# SO_DO_DK_TONG_THE_MAY_GHI_HINH_9_9_2021.net
KiCad netlist of a schematic drawn in Altium Designer
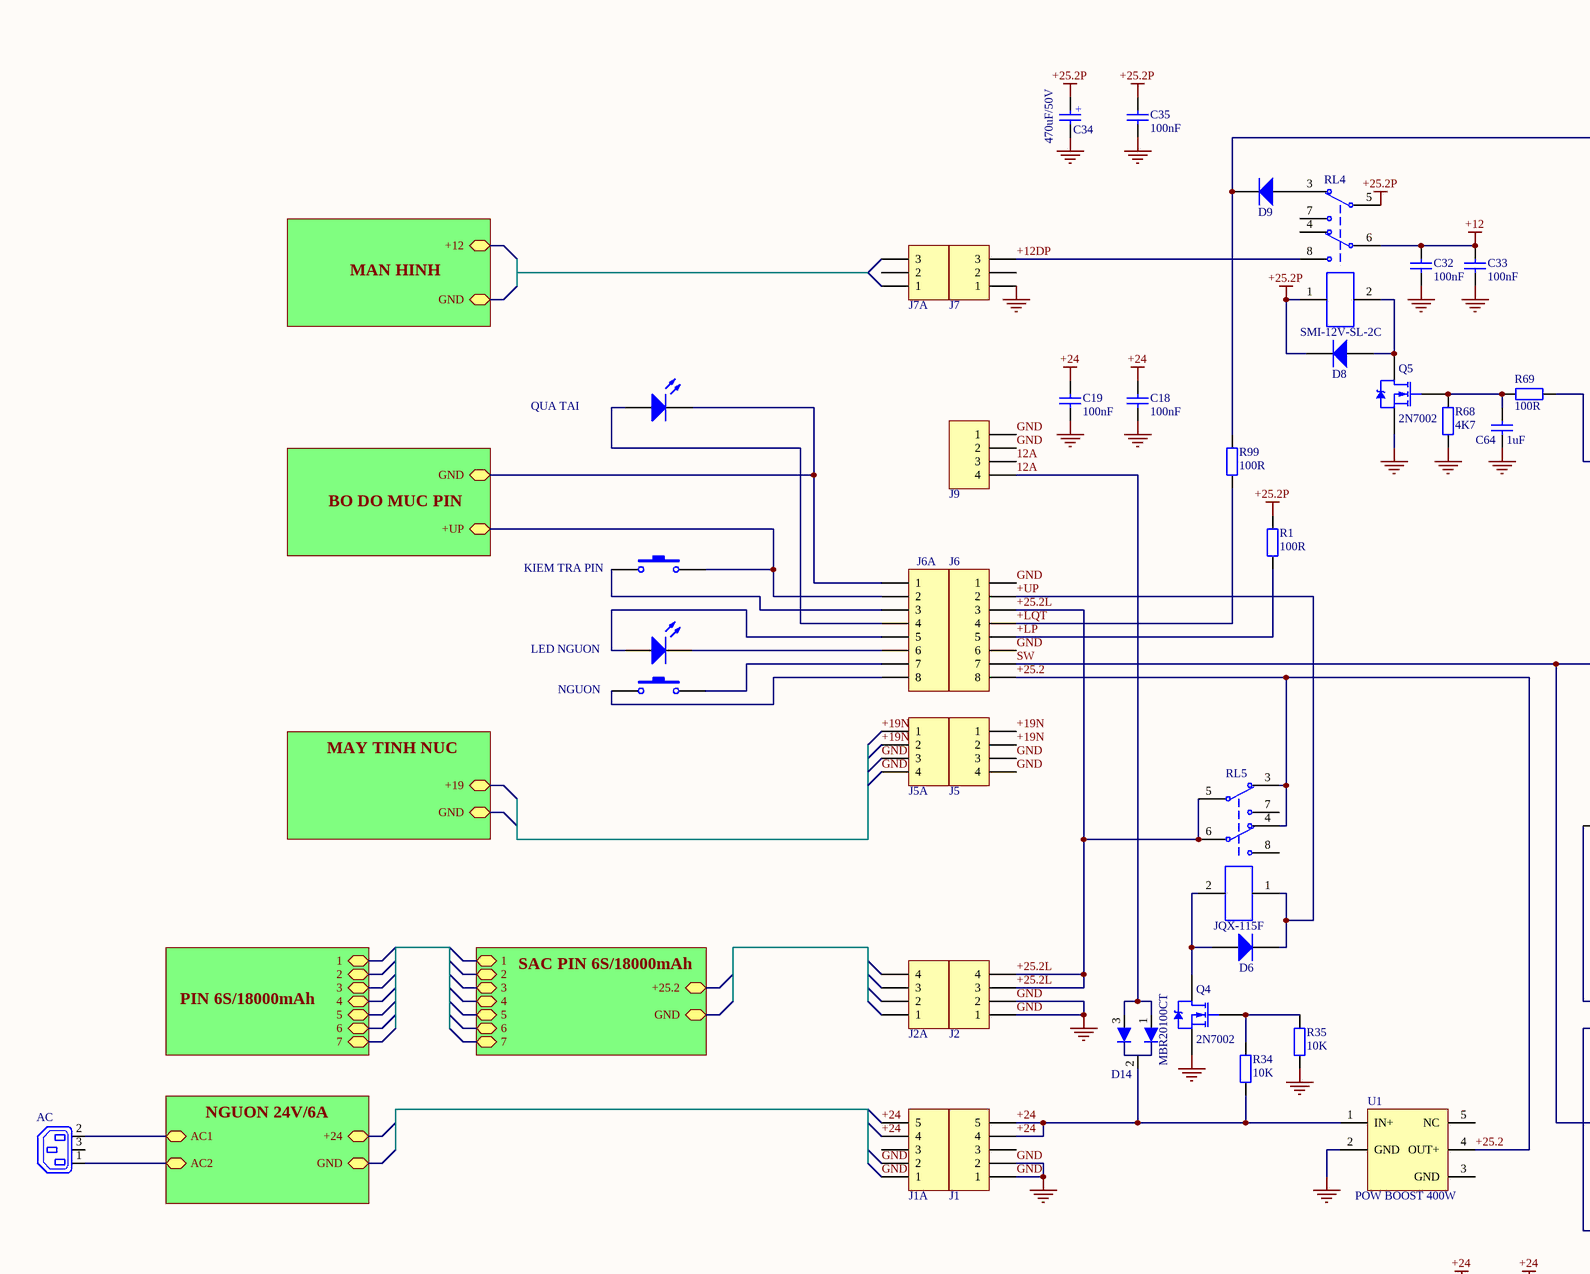
[diagram p0: SO_DO_DK_TONG_THE_MAY_GHI_HINH_9_9_2021.SchDoc, top left]
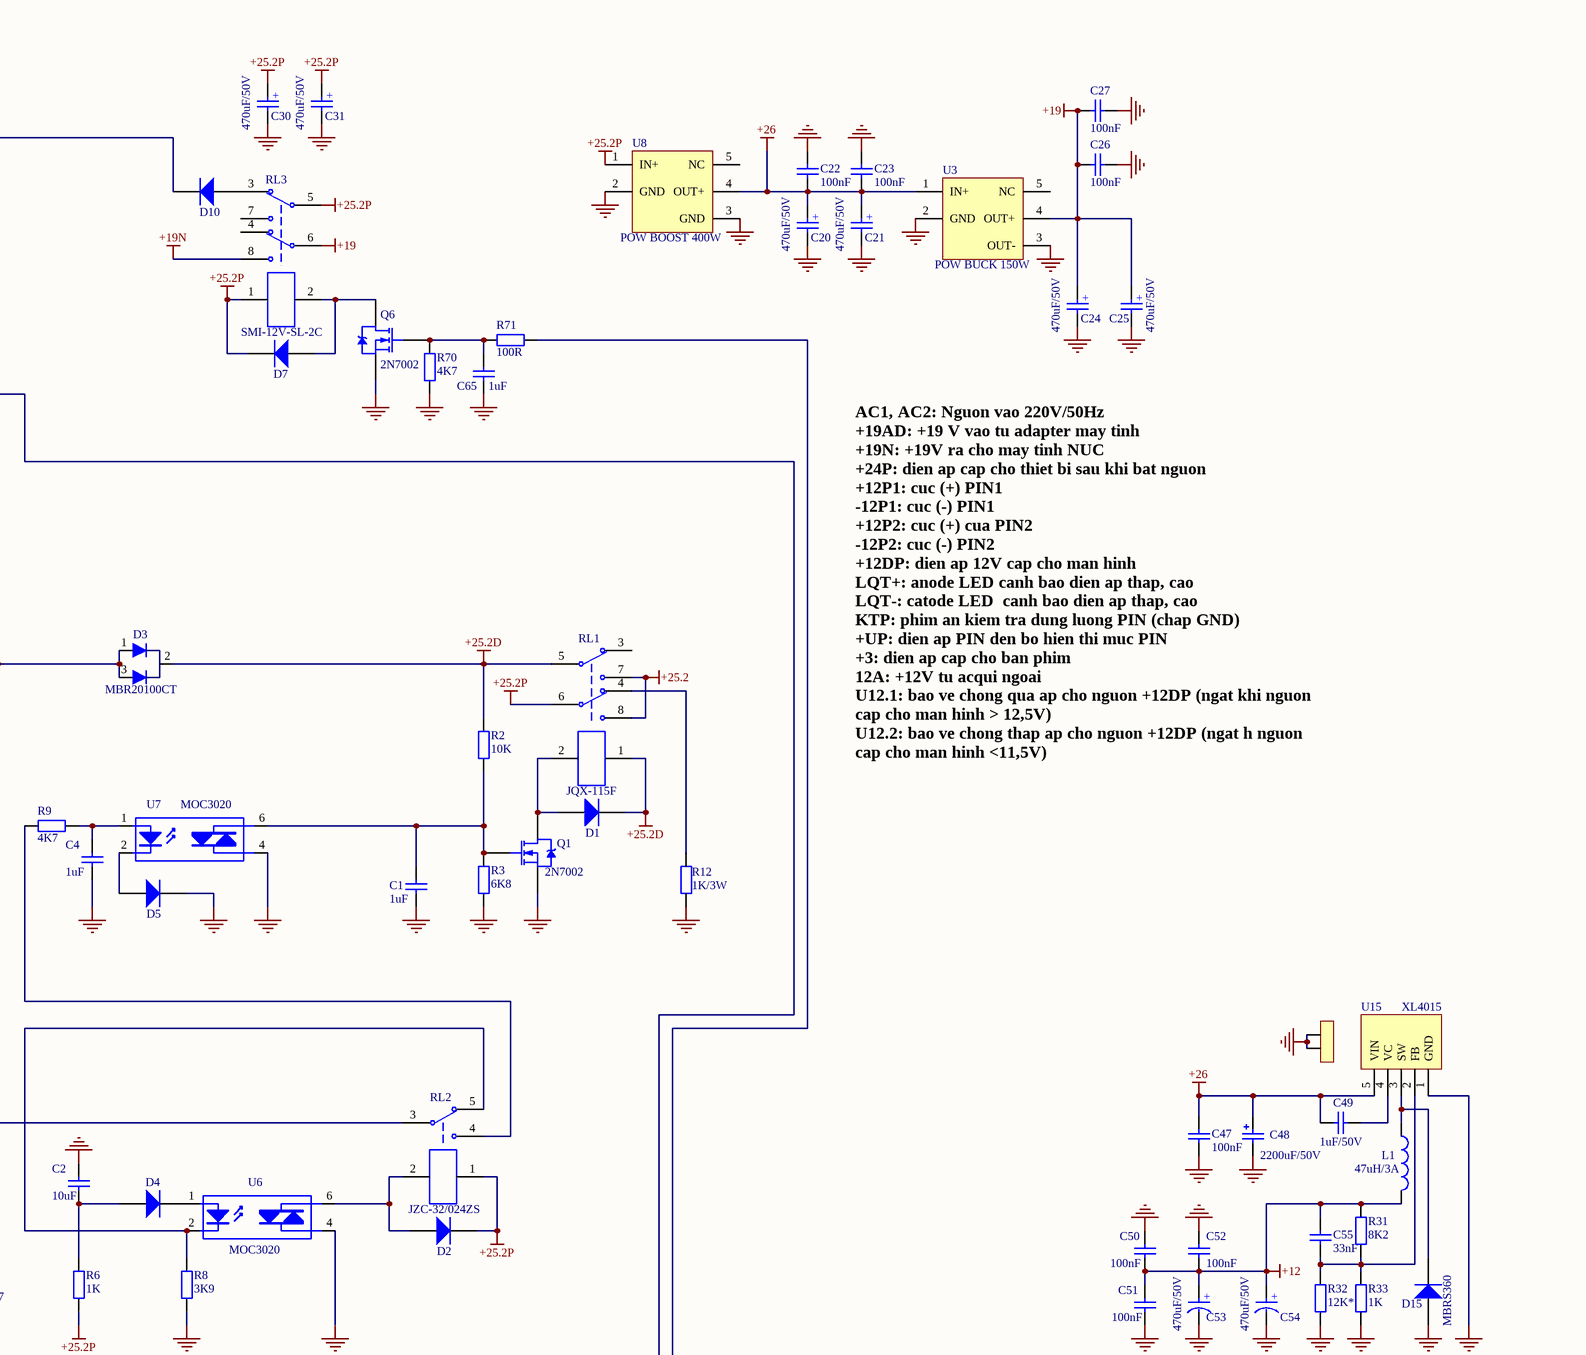
[diagram p1: SO_DO_DK_TONG_THE_MAY_GHI_HINH_9_9_2021.SchDoc, top right]
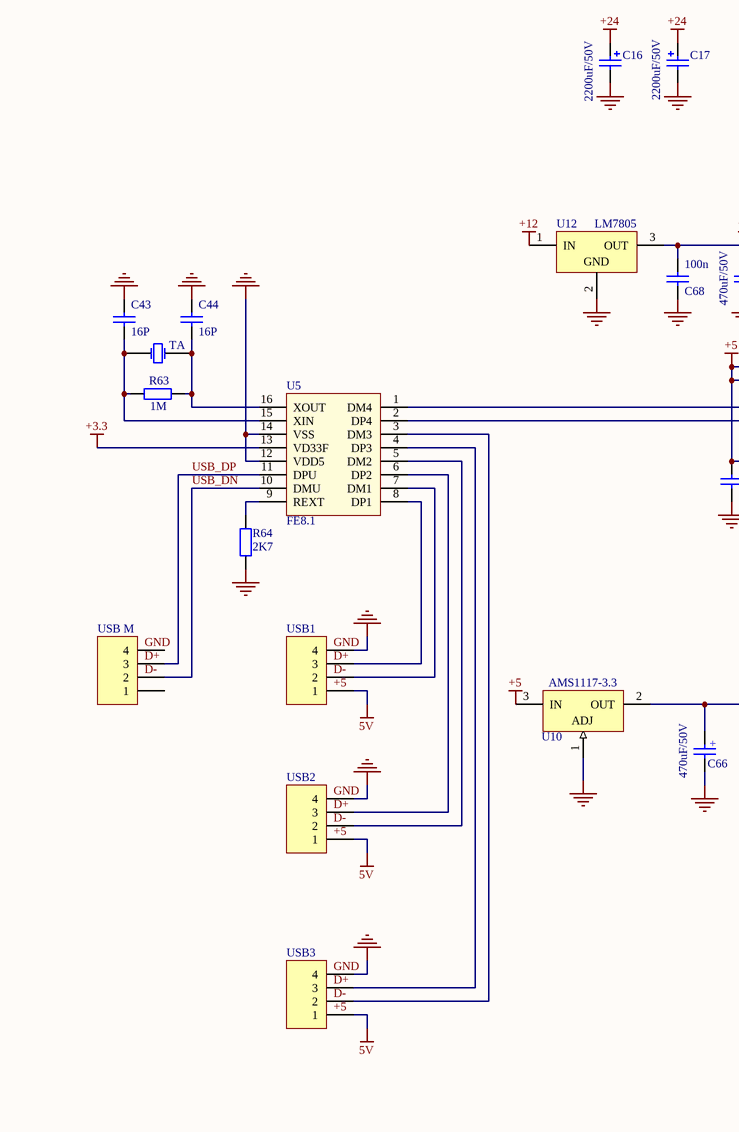
[diagram p2: SO_DO_DK_TONG_THE_MAY_GHI_HINH_9_9_2021.SchDoc, bottom left]
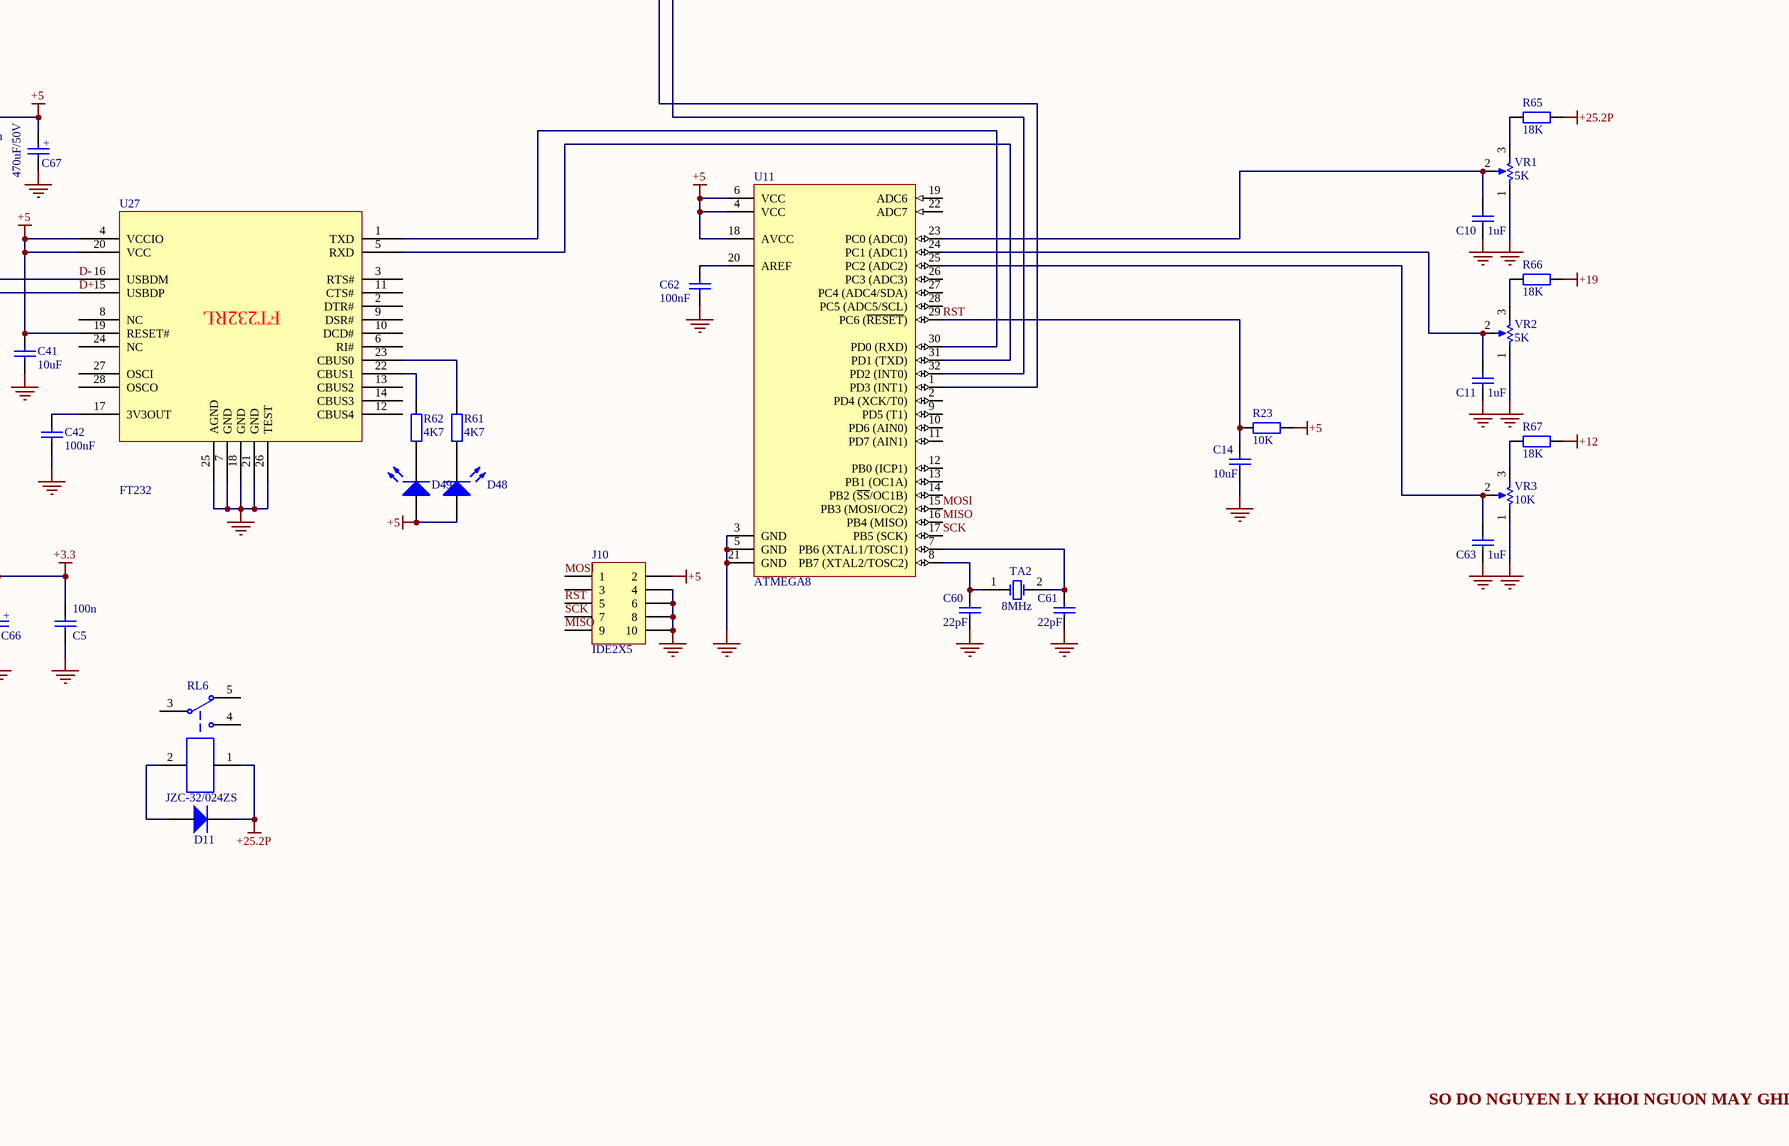
[diagram p3: SO_DO_DK_TONG_THE_MAY_GHI_HINH_9_9_2021.SchDoc, bottom right]

(export (version "E")
  (design (tool "Eeschema 10.0.6"))
  (components
    (comp (ref "AC")
      (value "GN1")
      (footprint "IEC7-2H3")
      (description "IEC Mains Power Outlet, EN60 320-2-2 F Class I, PC Flange Rear Mount, Chassis Socket")
      (fields (field (name "PUBLISHER") "Altium Limited"))
      (libsource (lib "Miscellaneous Connectors") (part "Plug AC Female"))
    )
    (comp (ref "C1")
      (value "Tu_SMD")
      (footprint "RC_SMD")
      (fields (field (name "ALTIUM_UNNAMED_1") "1uF"))
      (libsource (lib "vnschlib") (part "Tu_SMD"))
    )
    (comp (ref "C2")
      (value "Tu_SMD")
      (footprint "RC_SMD")
      (fields (field (name "ALTIUM_UNNAMED_1") "10uF"))
      (libsource (lib "vnschlib") (part "Tu_SMD"))
    )
    (comp (ref "C4")
      (value "Tu_SMD")
      (footprint "RC_SMD")
      (fields (field (name "ALTIUM_UNNAMED_1") "1uF"))
      (libsource (lib "vnschlib") (part "Tu_SMD"))
    )
    (comp (ref "C5")
      (value "Tu_SMD")
      (footprint "PCB_SMD_0805")
      (fields (field (name "ALTIUM_UNNAMED_1") "100n"))
      (libsource (lib "vnschlib") (part "Tu_SMD"))
    )
    (comp (ref "C10")
      (value "Tu_SMD")
      (footprint "RC_SMD")
      (fields (field (name "ALTIUM_UNNAMED_1") "1uF"))
      (libsource (lib "vnschlib") (part "Tu_SMD"))
    )
    (comp (ref "C11")
      (value "Tu_SMD")
      (footprint "RC_SMD")
      (fields (field (name "ALTIUM_UNNAMED_1") "1uF"))
      (libsource (lib "vnschlib") (part "Tu_SMD"))
    )
    (comp (ref "C14")
      (value "Tu_SMD")
      (footprint "PCB_SMD_0805")
      (fields (field (name "ALTIUM_UNNAMED_1") "10uF"))
      (libsource (lib "vnschlib") (part "Tu_SMD"))
    )
    (comp (ref "C16")
      (value "2200uF/50V")
      (footprint "tu_2200u/35")
      (fields (field (name "ALTIUM_UNNAMED_1") "2200uF/50V"))
      (libsource (lib "vnschlib") (part "Tu 2200uF/50V"))
    )
    (comp (ref "C17")
      (value "2200uF/50V")
      (footprint "tu_2200u/35")
      (fields (field (name "ALTIUM_UNNAMED_1") "2200uF/50V"))
      (libsource (lib "vnschlib") (part "Tu 2200uF/50V"))
    )
    (comp (ref "C18")
      (value "Tu_mica_100n")
      (footprint "RAD_0.3")
      (fields (field (name "ALTIUM_UNNAMED_1") "100nF"))
      (libsource (lib "vnschlib") (part "Tu_mica_100n"))
    )
    (comp (ref "C19")
      (value "Tu_mica_100n")
      (footprint "RAD_0.3")
      (fields (field (name "ALTIUM_UNNAMED_1") "100nF"))
      (libsource (lib "vnschlib") (part "Tu_mica_100n"))
    )
    (comp (ref "C20")
      (value "Tu_470u")
      (footprint "TU 470uF/50V")
      (fields (field (name "ALTIUM_UNNAMED_1") "470uF/50V"))
      (libsource (lib "") (part "Tu_470u_1"))
    )
    (comp (ref "C21")
      (value "Tu_470u")
      (footprint "TU 470uF/50V")
      (fields (field (name "ALTIUM_UNNAMED_1") "470uF/50V"))
      (libsource (lib "") (part "Tu_470u_1"))
    )
    (comp (ref "C22")
      (value "Tu_mica_100n")
      (footprint "RAD_0.3")
      (fields (field (name "ALTIUM_UNNAMED_1") "100nF"))
      (libsource (lib "vnschlib") (part "Tu_mica_100n"))
    )
    (comp (ref "C23")
      (value "Tu_mica_100n")
      (footprint "RAD_0.3")
      (fields (field (name "ALTIUM_UNNAMED_1") "100nF"))
      (libsource (lib "vnschlib") (part "Tu_mica_100n"))
    )
    (comp (ref "C24")
      (value "Tu_470u")
      (footprint "TU 470uF/50V")
      (fields (field (name "ALTIUM_UNNAMED_1") "470uF/50V"))
      (libsource (lib "") (part "Tu_470u_1"))
    )
    (comp (ref "C25")
      (value "Tu_470u")
      (footprint "TU 470uF/50V")
      (fields (field (name "ALTIUM_UNNAMED_1") "470uF/50V"))
      (libsource (lib "") (part "Tu_470u_1"))
    )
    (comp (ref "C26")
      (value "Tu_mica_100n")
      (footprint "RAD_0.3")
      (fields (field (name "ALTIUM_UNNAMED_1") "100nF"))
      (libsource (lib "vnschlib") (part "Tu_mica_100n"))
    )
    (comp (ref "C27")
      (value "Tu_mica_100n")
      (footprint "RAD_0.3")
      (fields (field (name "ALTIUM_UNNAMED_1") "100nF"))
      (libsource (lib "vnschlib") (part "Tu_mica_100n"))
    )
    (comp (ref "C30")
      (value "Tu_470u")
      (footprint "TU 470uF/50V")
      (fields (field (name "ALTIUM_UNNAMED_1") "470uF/50V"))
      (libsource (lib "") (part "Tu_470u_1"))
    )
    (comp (ref "C31")
      (value "Tu_470u")
      (footprint "TU 470uF/50V")
      (fields (field (name "ALTIUM_UNNAMED_1") "470uF/50V"))
      (libsource (lib "") (part "Tu_470u_1"))
    )
    (comp (ref "C32")
      (value "Tu_mica_100n")
      (footprint "RAD_0.3")
      (fields (field (name "ALTIUM_UNNAMED_1") "100nF"))
      (libsource (lib "vnschlib") (part "Tu_mica_100n"))
    )
    (comp (ref "C33")
      (value "Tu_mica_100n")
      (footprint "RAD_0.3")
      (fields (field (name "ALTIUM_UNNAMED_1") "100nF"))
      (libsource (lib "vnschlib") (part "Tu_mica_100n"))
    )
    (comp (ref "C34")
      (value "Tu_470u")
      (footprint "TU 470uF/50V")
      (fields (field (name "ALTIUM_UNNAMED_1") "470uF/50V"))
      (libsource (lib "") (part "Tu_470u_1"))
    )
    (comp (ref "C35")
      (value "Tu_mica_100n")
      (footprint "RAD_0.3")
      (fields (field (name "ALTIUM_UNNAMED_1") "100nF"))
      (libsource (lib "vnschlib") (part "Tu_mica_100n"))
    )
    (comp (ref "C41")
      (value "Tu_SMD")
      (footprint "PCB_SMD_0805")
      (fields (field (name "ALTIUM_UNNAMED_1") "10uF"))
      (libsource (lib "vnschlib") (part "Tu_SMD"))
    )
    (comp (ref "C42")
      (value "Tu_SMD")
      (footprint "PCB_SMD_0805")
      (fields (field (name "ALTIUM_UNNAMED_1") "100nF"))
      (libsource (lib "vnschlib") (part "Tu_SMD"))
    )
    (comp (ref "C43")
      (value "Tu_SMD")
      (footprint "PCB_SMD_0805")
      (fields (field (name "ALTIUM_UNNAMED_1") "16P"))
      (libsource (lib "vnschlib") (part "Tu_SMD"))
    )
    (comp (ref "C44")
      (value "Tu_SMD")
      (footprint "PCB_SMD_0805")
      (fields (field (name "ALTIUM_UNNAMED_1") "16P"))
      (libsource (lib "vnschlib") (part "Tu_SMD"))
    )
    (comp (ref "C47")
      (value "Tu_mica_100n")
      (footprint "RAD_0.3")
      (fields (field (name "ALTIUM_UNNAMED_1") "100nF"))
      (libsource (lib "vnschlib") (part "Tu_mica_100n"))
    )
    (comp (ref "C48")
      (value "2200uF/50V")
      (footprint "tu_2200u/35")
      (libsource (lib "vnschlib") (part "Tu 2200uF/50V"))
    )
    (comp (ref "C49")
      (value "Tu_SMD")
      (footprint "PCB_SMD_0805")
      (fields (field (name "ALTIUM_UNNAMED_1") "1uF/50V"))
      (libsource (lib "vnschlib") (part "Tu_SMD"))
    )
    (comp (ref "C50")
      (value "Tu_SMD")
      (footprint "PCB_SMD_0805")
      (fields (field (name "ALTIUM_UNNAMED_1") "100nF"))
      (libsource (lib "vnschlib") (part "Tu_SMD"))
    )
    (comp (ref "C51")
      (value "Tu_SMD")
      (footprint "PCB_SMD_0805")
      (fields (field (name "ALTIUM_UNNAMED_1") "100nF"))
      (libsource (lib "vnschlib") (part "Tu_SMD"))
    )
    (comp (ref "C52")
      (value "Tu_SMD")
      (footprint "PCB_SMD_0805")
      (fields (field (name "ALTIUM_UNNAMED_1") "100nF"))
      (libsource (lib "vnschlib") (part "Tu_SMD"))
    )
    (comp (ref "C53")
      (value "Tu_470u")
      (footprint "tu_470u_50V")
      (fields (field (name "ALTIUM_UNNAMED_1") "470uF/50V"))
      (libsource (lib "vnschlib") (part "Tu_470u"))
    )
    (comp (ref "C54")
      (value "Tu_470u")
      (footprint "tu_470u_50V")
      (fields (field (name "ALTIUM_UNNAMED_1") "470uF/50V"))
      (libsource (lib "vnschlib") (part "Tu_470u"))
    )
    (comp (ref "C55")
      (value "Tu_SMD")
      (footprint "RC_SMD")
      (fields (field (name "ALTIUM_UNNAMED_1") "33nF"))
      (libsource (lib "vnschlib") (part "Tu_SMD"))
    )
    (comp (ref "C60")
      (value "Tu_SMD")
      (footprint "PCB_SMD_0805")
      (fields (field (name "ALTIUM_UNNAMED_1") "22pF"))
      (libsource (lib "vnschlib") (part "Tu_SMD"))
    )
    (comp (ref "C61")
      (value "Tu_SMD")
      (footprint "PCB_SMD_0805")
      (fields (field (name "ALTIUM_UNNAMED_1") "22pF"))
      (libsource (lib "vnschlib") (part "Tu_SMD"))
    )
    (comp (ref "C62")
      (value "Tu_SMD")
      (footprint "PCB_SMD_0805")
      (fields (field (name "ALTIUM_UNNAMED_1") "100nF"))
      (libsource (lib "vnschlib") (part "Tu_SMD"))
    )
    (comp (ref "C63")
      (value "Tu_SMD")
      (footprint "RC_SMD")
      (fields (field (name "ALTIUM_UNNAMED_1") "1uF"))
      (libsource (lib "vnschlib") (part "Tu_SMD"))
    )
    (comp (ref "C64")
      (value "Tu_SMD")
      (footprint "RC_SMD")
      (fields (field (name "ALTIUM_UNNAMED_1") "1uF"))
      (libsource (lib "vnschlib") (part "Tu_SMD"))
    )
    (comp (ref "C65")
      (value "Tu_SMD")
      (footprint "RC_SMD")
      (fields (field (name "ALTIUM_UNNAMED_1") "1uF"))
      (libsource (lib "vnschlib") (part "Tu_SMD"))
    )
    (comp (ref "C66")
      (value "Tu_470u")
      (footprint "TU 470uF/50V")
      (fields (field (name "ALTIUM_UNNAMED_1") "470uF/50V"))
      (libsource (lib "") (part "Tu_470u_1"))
    )
    (comp (ref "C67")
      (value "Tu_470u")
      (footprint "TU 470uF/50V")
      (fields (field (name "ALTIUM_UNNAMED_1") "470uF/50V"))
      (libsource (lib "") (part "Tu_470u_1"))
    )
    (comp (ref "C68")
      (value "Tu_SMD")
      (footprint "PCB_SMD_0805")
      (fields (field (name "ALTIUM_UNNAMED_1") "100n"))
      (libsource (lib "vnschlib") (part "Tu_SMD"))
    )
    (comp (ref "D1") (value "Diode_1A") (footprint "Diode_1A") (libsource (lib "vnschlib") (part "Diode_1A")))
    (comp (ref "D2") (value "Diode_1A") (footprint "Diode_1A") (libsource (lib "vnschlib") (part "Diode_1A")))
    (comp (ref "D3") (value "MBR20100CT") (footprint "TO220") (libsource (lib "vnschlib") (part "MUR3020")))
    (comp (ref "D4") (value "Diode_1A") (footprint "Diode_1A") (libsource (lib "vnschlib") (part "Diode_1A")))
    (comp (ref "D5") (value "Diode_1A") (footprint "Diode_1A") (libsource (lib "vnschlib") (part "Diode_1A")))
    (comp (ref "D6") (value "Diode_1A") (footprint "Diode_1A") (libsource (lib "vnschlib") (part "Diode_1A")))
    (comp (ref "D7") (value "Diode_1A") (footprint "Diode_1A") (libsource (lib "vnschlib") (part "Diode_1A")))
    (comp (ref "D8") (value "Diode_1A") (footprint "Diode_1A") (libsource (lib "vnschlib") (part "Diode_1A")))
    (comp (ref "D9") (value "Diode_1A") (footprint "Diode_1A") (libsource (lib "vnschlib") (part "Diode_1A")))
    (comp (ref "D10")
      (value "Diode_1A")
      (footprint "Diode_1A")
      (libsource (lib "vnschlib") (part "Diode_1A"))
    )
    (comp (ref "D11")
      (value "Diode_1A")
      (footprint "Diode_1A")
      (libsource (lib "vnschlib") (part "Diode_1A"))
    )
    (comp (ref "D14") (value "MBR20100CT") (footprint "TO220") (libsource (lib "vnschlib") (part "MUR3020")))
    (comp (ref "D15") (value "MBRS360") (footprint "DO-214AA") (libsource (lib "vnschlib") (part "Diode 5A")))
    (comp (ref "D48") (value "LED") (footprint "LED SMD") (libsource (lib "vnschlib") (part "LED_SMD")))
    (comp (ref "D49") (value "LED") (footprint "LED SMD") (libsource (lib "vnschlib") (part "LED_SMD")))
    (comp (ref "J1")
      (value "Header 3.96, 5P")
      (footprint "H396_5P")
      (libsource (lib "vnschlib") (part "H396_5P"))
    )
    (comp (ref "J1A") (value "Header 3.96, 5P") (footprint "H396_5P") (libsource (lib "") (part "H396_5P_1")))
    (comp (ref "J2") (value "Header 3.96, 4P") (footprint "H396_4P") (libsource (lib "") (part "H396_4P_3")))
    (comp (ref "J2A") (value "Header 3.96, 4P") (footprint "H396_4P") (libsource (lib "") (part "H396_4P_2")))
    (comp (ref "J5")
      (value "Header 3.96, 4P")
      (footprint "H396_4P")
      (libsource (lib "vnschlib") (part "H396_4P"))
    )
    (comp (ref "J5A") (value "Header 3.96, 4P") (footprint "H396_4P") (libsource (lib "") (part "H396_4P_1")))
    (comp (ref "J6") (value "Header 3.96, 8P") (footprint "H396_8P") (libsource (lib "") (part "H396_8P_1")))
    (comp (ref "J6A")
      (value "Header 3.96, 8P")
      (footprint "H396_8P")
      (libsource (lib "vnschlib") (part "H396_8P"))
    )
    (comp (ref "J7") (value "Header 3.96, 3P") (footprint "H396_3P") (libsource (lib "") (part "H396_3P_1")))
    (comp (ref "J7A")
      (value "Header 3.96, 3P")
      (footprint "H396_3P")
      (libsource (lib "vnschlib") (part "H396_3P"))
    )
    (comp (ref "J9")
      (value "Header 3.96, 4P")
      (footprint "H396_4P")
      (libsource (lib "vnschlib") (part "H396_4P"))
    )
    (comp (ref "J10")
      (value "IDE2X5")
      (footprint "IDE 2x5 DUC THANG")
      (libsource (lib "vnschlib") (part "IDE2X5"))
    )
    (comp (ref "KIEM TRA PIN")
      (value "SW-PB")
      (footprint "SPST-2")
      (description "Switch")
      (fields (field (name "PUBLISHER") "Altium Limited"))
      (libsource (lib "Miscellaneous Devices") (part "SW-PB"))
    )
    (comp (ref "L1")
      (value "47uH/3A")
      (footprint "CUON CAM 3A SMD")
      (libsource (lib "vnschlib") (part "CUON CAM 3A SMD"))
    )
    (comp (ref "LED NGUON")
      (value "LED0")
      (footprint "LED-0")
      (description "Typical INFRARED GaAs LED")
      (fields (field (name "PUBLISHER") "Altium Limited"))
      (libsource (lib "Miscellaneous Devices") (part "LED0"))
    )
    (comp (ref "NGUON")
      (value "SW-PB")
      (footprint "SPST-2")
      (description "Switch")
      (fields (field (name "PUBLISHER") "Altium Limited"))
      (libsource (lib "Miscellaneous Devices") (part "SW-PB"))
    )
    (comp (ref "Q1") (value "2N7002") (footprint "SOT23") (libsource (lib "vnschlib") (part "2N7002")))
    (comp (ref "Q4") (value "2N7002") (footprint "SOT23") (libsource (lib "vnschlib") (part "2N7002")))
    (comp (ref "Q5") (value "2N7002") (footprint "SOT23") (libsource (lib "vnschlib") (part "2N7002")))
    (comp (ref "Q6") (value "2N7002") (footprint "SOT23") (libsource (lib "vnschlib") (part "2N7002")))
    (comp (ref "QUA TAI")
      (value "LED0")
      (footprint "LED-0")
      (description "Typical INFRARED GaAs LED")
      (fields (field (name "PUBLISHER") "Altium Limited"))
      (libsource (lib "Miscellaneous Devices") (part "LED0"))
    )
    (comp (ref "R1")
      (value "Tro_SMD")
      (footprint "RC_SMD")
      (fields (field (name "ALTIUM_UNNAMED_1") "100R"))
      (libsource (lib "vnschlib") (part "Tro_SMD"))
    )
    (comp (ref "R2")
      (value "Tro_SMD")
      (footprint "RC_SMD")
      (fields (field (name "ALTIUM_UNNAMED_1") "10K"))
      (libsource (lib "vnschlib") (part "Tro_SMD"))
    )
    (comp (ref "R3")
      (value "Tro_SMD")
      (footprint "RC_SMD")
      (fields (field (name "ALTIUM_UNNAMED_1") "6K8"))
      (libsource (lib "vnschlib") (part "Tro_SMD"))
    )
    (comp (ref "R6")
      (value "Tro_SMD")
      (footprint "RC_SMD")
      (fields (field (name "ALTIUM_UNNAMED_1") "1K"))
      (libsource (lib "vnschlib") (part "Tro_SMD"))
    )
    (comp (ref "R8")
      (value "Tro_SMD")
      (footprint "RC_SMD")
      (fields (field (name "ALTIUM_UNNAMED_1") "3K9"))
      (libsource (lib "vnschlib") (part "Tro_SMD"))
    )
    (comp (ref "R9")
      (value "Tro_SMD")
      (footprint "RC_SMD")
      (fields (field (name "ALTIUM_UNNAMED_1") "4K7"))
      (libsource (lib "vnschlib") (part "Tro_SMD"))
    )
    (comp (ref "R12")
      (value "Dien_tro_2W")
      (footprint "R-2W")
      (fields (field (name "ALTIUM_UNNAMED_1") "1K/3W"))
      (libsource (lib "vnschlib") (part "Dien_tro_2W"))
    )
    (comp (ref "R23")
      (value "Tro_SMD")
      (footprint "PCB_SMD_0805")
      (fields (field (name "ALTIUM_UNNAMED_1") "10K"))
      (libsource (lib "vnschlib") (part "Tro_SMD"))
    )
    (comp (ref "R31")
      (value "Tro_SMD")
      (footprint "PCB_SMD_0805")
      (fields (field (name "ALTIUM_UNNAMED_1") "8K2"))
      (libsource (lib "vnschlib") (part "Tro_SMD"))
    )
    (comp (ref "R32")
      (value "Tro_SMD")
      (footprint "PCB_SMD_0805")
      (fields (field (name "ALTIUM_UNNAMED_1") "12K*"))
      (libsource (lib "vnschlib") (part "Tro_SMD"))
    )
    (comp (ref "R33")
      (value "Tro_SMD")
      (footprint "PCB_SMD_0805")
      (fields (field (name "ALTIUM_UNNAMED_1") "1K"))
      (libsource (lib "vnschlib") (part "Tro_SMD"))
    )
    (comp (ref "R34")
      (value "Tro_SMD")
      (footprint "RC_SMD")
      (fields (field (name "ALTIUM_UNNAMED_1") "10K"))
      (libsource (lib "vnschlib") (part "Tro_SMD"))
    )
    (comp (ref "R35")
      (value "Tro_SMD")
      (footprint "RC_SMD")
      (fields (field (name "ALTIUM_UNNAMED_1") "10K"))
      (libsource (lib "vnschlib") (part "Tro_SMD"))
    )
    (comp (ref "R61")
      (value "Tro_SMD")
      (footprint "RC_SMD")
      (fields (field (name "ALTIUM_UNNAMED_1") "4K7"))
      (libsource (lib "vnschlib") (part "Tro_SMD"))
    )
    (comp (ref "R62")
      (value "Tro_SMD")
      (footprint "RC_SMD")
      (fields (field (name "ALTIUM_UNNAMED_1") "4K7"))
      (libsource (lib "vnschlib") (part "Tro_SMD"))
    )
    (comp (ref "R63")
      (value "Tro_SMD")
      (footprint "RC_SMD")
      (fields (field (name "ALTIUM_UNNAMED_1") "1M"))
      (libsource (lib "vnschlib") (part "Tro_SMD"))
    )
    (comp (ref "R64")
      (value "Tro_SMD")
      (footprint "RC_SMD")
      (fields (field (name "ALTIUM_UNNAMED_1") "2K7"))
      (libsource (lib "vnschlib") (part "Tro_SMD"))
    )
    (comp (ref "R65")
      (value "Tro_SMD")
      (footprint "PCB_SMD_0805")
      (fields (field (name "ALTIUM_UNNAMED_1") "18K"))
      (libsource (lib "vnschlib") (part "Tro_SMD"))
    )
    (comp (ref "R66")
      (value "Tro_SMD")
      (footprint "PCB_SMD_0805")
      (fields (field (name "ALTIUM_UNNAMED_1") "18K"))
      (libsource (lib "vnschlib") (part "Tro_SMD"))
    )
    (comp (ref "R67")
      (value "Tro_SMD")
      (footprint "PCB_SMD_0805")
      (fields (field (name "ALTIUM_UNNAMED_1") "18K"))
      (libsource (lib "vnschlib") (part "Tro_SMD"))
    )
    (comp (ref "R68")
      (value "Tro_SMD")
      (footprint "PCB_SMD_0805")
      (fields (field (name "ALTIUM_UNNAMED_1") "4K7"))
      (libsource (lib "vnschlib") (part "Tro_SMD"))
    )
    (comp (ref "R69")
      (value "Tro_SMD")
      (footprint "PCB_SMD_0805")
      (fields (field (name "ALTIUM_UNNAMED_1") "100R"))
      (libsource (lib "vnschlib") (part "Tro_SMD"))
    )
    (comp (ref "R70")
      (value "Tro_SMD")
      (footprint "PCB_SMD_0805")
      (fields (field (name "ALTIUM_UNNAMED_1") "4K7"))
      (libsource (lib "vnschlib") (part "Tro_SMD"))
    )
    (comp (ref "R71")
      (value "Tro_SMD")
      (footprint "PCB_SMD_0805")
      (fields (field (name "ALTIUM_UNNAMED_1") "100R"))
      (libsource (lib "vnschlib") (part "Tro_SMD"))
    )
    (comp (ref "R99")
      (value "Tro_SMD")
      (footprint "RC_SMD")
      (fields (field (name "ALTIUM_UNNAMED_1") "100R"))
      (libsource (lib "vnschlib") (part "Tro_SMD"))
    )
    (comp (ref "RL1")
      (value "JQX-115F")
      (footprint "Role_SMI-24VDC-SL-2C")
      (libsource (lib "vnschlib") (part "Role_SMI_24V_SL_2C"))
    )
    (comp (ref "RL2")
      (value "JZC-32/024ZS")
      (footprint "JZC-32F/024ZS")
      (libsource (lib "vnschlib") (part "RELAY JZC-32/024ZS"))
    )
    (comp (ref "RL3")
      (value "SMI-12V-SL-2C")
      (footprint "Role_SMI-24VDC-SL-2C")
      (libsource (lib "") (part "Role_SMI_24V_SL_2C_1"))
    )
    (comp (ref "RL4")
      (value "SMI-12V-SL-2C")
      (footprint "Role_SMI-24VDC-SL-2C")
      (libsource (lib "") (part "Role_SMI_24V_SL_2C_1"))
    )
    (comp (ref "RL5")
      (value "JQX-115F")
      (footprint "Role_SMI-24VDC-SL-2C")
      (libsource (lib "vnschlib") (part "Role_SMI_24V_SL_2C"))
    )
    (comp (ref "RL6")
      (value "JZC-32/024ZS")
      (footprint "JZC-32F/024ZS")
      (libsource (lib "vnschlib") (part "RELAY JZC-32/024ZS"))
    )
    (comp (ref "TA") (value "TA") (footprint "PCB TA SMD") (libsource (lib "vnschlib") (part "TA")))
    (comp (ref "TA2") (value "8MHz") (footprint "TA") (libsource (lib "") (part "TA_1")))
    (comp (ref "TN2")
      (value "TAN NHIET CPU")
      (footprint "TAN_NHIET_CPU")
      (libsource (lib "vnschlib") (part "TAN NHIET CPU"))
    )
    (comp (ref "U1")
      (value "POW BOOST 400W")
      (footprint "PCB NGUON BOOST 400W")
      (libsource (lib "vnschlib") (part "Nguon BOOST 150W"))
    )
    (comp (ref "U3")
      (value "POW BUCK 150W")
      (footprint "PCB Nguon BUCK BOOST 150W")
      (libsource (lib "vnschlib") (part "Nguon BUCK 150W"))
    )
    (comp (ref "U5") (value "FE8.1") (footprint "PCB FE8.1") (libsource (lib "vnschlib") (part "FE8.1")))
    (comp (ref "U6") (value "MOC3020") (footprint "DIP6") (libsource (lib "vnschlib") (part "MOC3020")))
    (comp (ref "U7") (value "MOC3020") (footprint "DIP6") (libsource (lib "vnschlib") (part "MOC3020")))
    (comp (ref "U8")
      (value "POW BOOST 400W")
      (footprint "PCB NGUON BOOST 400W")
      (libsource (lib "vnschlib") (part "Nguon BOOST 150W"))
    )
    (comp (ref "U10")
      (value "AMS1117-3.3")
      (footprint "SOT-223VN")
      (libsource (lib "vnschlib") (part "LM317"))
    )
    (comp (ref "U11")
      (value "ATMEGA8")
      (footprint "ATMEGA8VN")
      (libsource (lib "vnschlib") (part "ATMEGA8VN"))
    )
    (comp (ref "U12") (value "LM7805") (footprint "TO-252") (libsource (lib "vnschlib") (part "L7805")))
    (comp (ref "U15") (value "XL4015") (footprint "TO-263-5L") (libsource (lib "vnschlib") (part "XL4015VN")))
    (comp (ref "U27") (value "FT232") (footprint "SSOP28") (libsource (lib "vnschlib") (part "FT232")))
    (comp (ref "USB M")
      (value "H4P254")
      (footprint "Jac_4P_nho")
      (libsource (lib "vnschlib") (part "H4P254"))
    )
    (comp (ref "USB1") (value "H4P254") (footprint "Jac_4P_nho") (libsource (lib "vnschlib") (part "H4P254")))
    (comp (ref "USB2") (value "H4P254") (footprint "Jac_4P_nho") (libsource (lib "vnschlib") (part "H4P254")))
    (comp (ref "USB3") (value "H4P254") (footprint "Jac_4P_nho") (libsource (lib "vnschlib") (part "H4P254")))
    (comp (ref "VR1")
      (value "Chiet_ap_vi_chinh")
      (footprint "PCB Chiet ap vi chinh 3296")
      (fields (field (name "ALTIUM_UNNAMED_1") "5K"))
      (libsource (lib "vnschlib") (part "Chiet_ap_vi_chinh"))
    )
    (comp (ref "VR2")
      (value "Chiet_ap_vi_chinh")
      (footprint "PCB Chiet ap vi chinh 3296")
      (fields (field (name "ALTIUM_UNNAMED_1") "5K"))
      (libsource (lib "vnschlib") (part "Chiet_ap_vi_chinh"))
    )
    (comp (ref "VR3")
      (value "Chiet_ap_vi_chinh")
      (footprint "PCB Chiet ap vi chinh 3296")
      (fields (field (name "ALTIUM_UNNAMED_1") "10K"))
      (libsource (lib "vnschlib") (part "Chiet_ap_vi_chinh"))
    )
  )
  (nets
    (net (code "1") (name "+3.3") (class "Default")
      (node (ref "C5") (pin "2") (pinfunction "2_2") (pintype "passive"))
      (node (ref "C66") (pin "1") (pinfunction "1_1") (pintype "passive"))
      (node (ref "U10") (pin "2") (pinfunction "OUT_2") (pintype "power_in"))
      (node (ref "U5") (pin "13") (pinfunction "VD33F_13") (pintype "passive"))
    )
    (net (code "2") (name "+5") (class "Default")
      (node (ref "C41") (pin "1") (pinfunction "1_1") (pintype "passive"))
      (node (ref "C67") (pin "1") (pinfunction "1_1") (pintype "passive"))
      (node (ref "C68") (pin "2") (pinfunction "2_2") (pintype "passive"))
      (node (ref "D48") (pin "1") (pinfunction "A_1") (pintype "passive"))
      (node (ref "D49") (pin "1") (pinfunction "A_1") (pintype "passive"))
      (node (ref "J10") (pin "2") (pinfunction "2_2") (pintype "passive"))
      (node (ref "R23") (pin "2") (pinfunction "2_2") (pintype "passive"))
      (node (ref "U10") (pin "3") (pinfunction "IN_3") (pintype "power_in"))
      (node (ref "U11") (pin "18") (pinfunction "AVCC_18") (pintype "power_in"))
      (node (ref "U11") (pin "4") (pinfunction "VCC_4") (pintype "power_in"))
      (node (ref "U11") (pin "6") (pinfunction "VCC_6") (pintype "power_in"))
      (node (ref "U12") (pin "3") (pinfunction "OUT_3") (pintype "power_in"))
      (node (ref "U27") (pin "19") (pinfunction "RESET#_19") (pintype "passive"))
      (node (ref "U27") (pin "20") (pinfunction "VCC_20") (pintype "passive"))
      (node (ref "U27") (pin "4") (pinfunction "VCCIO_4") (pintype "passive"))
    )
    (net (code "3") (name "+12") (class "Default")
      (node (ref "C32") (pin "1") (pinfunction "1_1") (pintype "passive"))
      (node (ref "C33") (pin "2") (pinfunction "2_2") (pintype "passive"))
      (node (ref "C50") (pin "1") (pinfunction "1_1") (pintype "passive"))
      (node (ref "C51") (pin "1") (pinfunction "1_1") (pintype "passive"))
      (node (ref "C52") (pin "1") (pinfunction "1_1") (pintype "passive"))
      (node (ref "C53") (pin "1") (pinfunction "1_1") (pintype "passive"))
      (node (ref "C54") (pin "1") (pinfunction "1_1") (pintype "passive"))
      (node (ref "C55") (pin "2") (pinfunction "2_2") (pintype "passive"))
      (node (ref "L1") (pin "2") (pinfunction "2_2") (pintype "passive"))
      (node (ref "R31") (pin "2") (pinfunction "2_2") (pintype "passive"))
      (node (ref "R67") (pin "2") (pinfunction "2_2") (pintype "passive"))
      (node (ref "RL4") (pin "6") (pinfunction "6_6") (pintype "passive"))
      (node (ref "U12") (pin "1") (pinfunction "IN_1") (pintype "power_in"))
    )
    (net (code "4") (name "+19") (class "Default")
      (node (ref "C24") (pin "1") (pinfunction "1_1") (pintype "passive"))
      (node (ref "C25") (pin "1") (pinfunction "1_1") (pintype "passive"))
      (node (ref "C26") (pin "1") (pinfunction "1_1") (pintype "passive"))
      (node (ref "C27") (pin "2") (pinfunction "2_2") (pintype "passive"))
      (node (ref "R66") (pin "2") (pinfunction "2_2") (pintype "passive"))
      (node (ref "RL3") (pin "6") (pinfunction "6_6") (pintype "passive"))
      (node (ref "U3") (pin "4") (pinfunction "OUT+_4") (pintype "passive"))
    )
    (net (code "5") (name "+19N") (class "Default")
      (node (ref "J5") (pin "1") (pinfunction "1_1") (pintype "passive"))
      (node (ref "J5") (pin "2") (pinfunction "2_2") (pintype "passive"))
      (node (ref "J5A") (pin "1") (pinfunction "1_1") (pintype "passive"))
      (node (ref "J5A") (pin "2") (pinfunction "2_2") (pintype "passive"))
      (node (ref "RL3") (pin "8") (pinfunction "8_8") (pintype "passive"))
    )
    (net (code "6") (name "+24") (class "Default")
      (node (ref "C16") (pin "1") (pinfunction "1_1") (pintype "passive"))
      (node (ref "C17") (pin "1") (pinfunction "1_1") (pintype "passive"))
      (node (ref "C18") (pin "2") (pinfunction "2_2") (pintype "passive"))
      (node (ref "C19") (pin "2") (pinfunction "2_2") (pintype "passive"))
      (node (ref "D14") (pin "2") (pinfunction "2_2") (pintype "passive"))
      (node (ref "J1") (pin "4") (pinfunction "4_4") (pintype "passive"))
      (node (ref "J1") (pin "5") (pinfunction "5_5") (pintype "passive"))
      (node (ref "J1A") (pin "4") (pinfunction "4_4") (pintype "passive"))
      (node (ref "J1A") (pin "5") (pinfunction "5_5") (pintype "passive"))
      (node (ref "R34") (pin "1") (pinfunction "1_1") (pintype "passive"))
      (node (ref "U1") (pin "1") (pinfunction "IN+_1") (pintype "passive"))
    )
    (net (code "7") (name "+25.2") (class "Default")
      (node (ref "J6") (pin "8") (pinfunction "8_8") (pintype "power_in"))
      (node (ref "RL1") (pin "7") (pinfunction "7_7") (pintype "passive"))
      (node (ref "RL1") (pin "8") (pinfunction "8_8") (pintype "passive"))
      (node (ref "RL5") (pin "3") (pinfunction "3_3") (pintype "passive"))
      (node (ref "RL5") (pin "4") (pinfunction "4_4") (pintype "passive"))
      (node (ref "U1") (pin "4") (pinfunction "OUT+_4") (pintype "passive"))
    )
    (net (code "8") (name "+25.2D") (class "Default")
      (node (ref "D1") (pin "2") (pinfunction "2_2") (pintype "passive"))
      (node (ref "D3") (pin "2") (pinfunction "2_2") (pintype "passive"))
      (node (ref "R2") (pin "1") (pinfunction "1_1") (pintype "passive"))
      (node (ref "RL1") (pin "1") (pinfunction "1_1") (pintype "passive"))
      (node (ref "RL1") (pin "5") (pinfunction "5_5") (pintype "passive"))
    )
    (net (code "9") (name "+25.2P") (class "Default")
      (node (ref "C30") (pin "1") (pinfunction "1_1") (pintype "passive"))
      (node (ref "C31") (pin "1") (pinfunction "1_1") (pintype "passive"))
      (node (ref "C34") (pin "1") (pinfunction "1_1") (pintype "passive"))
      (node (ref "C35") (pin "2") (pinfunction "2_2") (pintype "passive"))
      (node (ref "D11") (pin "2") (pinfunction "2_2") (pintype "passive"))
      (node (ref "D2") (pin "2") (pinfunction "2_2") (pintype "passive"))
      (node (ref "D7") (pin "2") (pinfunction "2_2") (pintype "passive"))
      (node (ref "D8") (pin "2") (pinfunction "2_2") (pintype "passive"))
      (node (ref "R1") (pin "2") (pinfunction "2_2") (pintype "passive"))
      (node (ref "R6") (pin "1") (pinfunction "1_1") (pintype "passive"))
      (node (ref "R65") (pin "2") (pinfunction "2_2") (pintype "passive"))
      (node (ref "RL1") (pin "6") (pinfunction "6_6") (pintype "passive"))
      (node (ref "RL2") (pin "1") (pinfunction "1_1") (pintype "passive"))
      (node (ref "RL3") (pin "1") (pinfunction "1_1") (pintype "passive"))
      (node (ref "RL3") (pin "5") (pinfunction "5_5") (pintype "passive"))
      (node (ref "RL4") (pin "1") (pinfunction "1_1") (pintype "passive"))
      (node (ref "RL4") (pin "5") (pinfunction "5_5") (pintype "passive"))
      (node (ref "RL6") (pin "1") (pinfunction "1_1") (pintype "passive"))
      (node (ref "U8") (pin "1") (pinfunction "IN+_1") (pintype "passive"))
    )
    (net (code "10") (name "+26") (class "Default")
      (node (ref "C20") (pin "1") (pinfunction "1_1") (pintype "passive"))
      (node (ref "C21") (pin "1") (pinfunction "1_1") (pintype "passive"))
      (node (ref "C22") (pin "2") (pinfunction "2_2") (pintype "passive"))
      (node (ref "C23") (pin "1") (pinfunction "1_1") (pintype "passive"))
      (node (ref "C47") (pin "2") (pinfunction "2_2") (pintype "passive"))
      (node (ref "C48") (pin "1") (pinfunction "1_1") (pintype "passive"))
      (node (ref "C49") (pin "1") (pinfunction "1_1") (pintype "passive"))
      (node (ref "U15") (pin "5") (pinfunction "VIN_5") (pintype "passive"))
      (node (ref "U3") (pin "1") (pinfunction "IN+_1") (pintype "passive"))
      (node (ref "U8") (pin "4") (pinfunction "OUT+_4") (pintype "passive"))
    )
    (net (code "12") (name "/+12DP") (class "Default")
      (node (ref "J7") (pin "3") (pinfunction "3_3") (pintype "passive"))
      (node (ref "RL4") (pin "8") (pinfunction "8_8") (pintype "passive"))
    )
    (net (code "15") (name "/+25.2L") (class "Default")
      (node (ref "J2") (pin "3") (pinfunction "3_3") (pintype "passive"))
      (node (ref "J2") (pin "4") (pinfunction "4_4") (pintype "passive"))
      (node (ref "J6") (pin "3") (pinfunction "3_3") (pintype "passive"))
      (node (ref "RL5") (pin "5") (pinfunction "5_5") (pintype "passive"))
      (node (ref "RL5") (pin "6") (pinfunction "6_6") (pintype "passive"))
    )
    (net (code "17") (name "/+LP") (class "Default")
      (node (ref "J6") (pin "5") (pinfunction "5_5") (pintype "passive"))
      (node (ref "R1") (pin "1") (pinfunction "1_1") (pintype "passive"))
    )
    (net (code "18") (name "/+LQT") (class "Default")
      (node (ref "J6") (pin "4") (pinfunction "4_4") (pintype "passive"))
      (node (ref "R99") (pin "1") (pinfunction "1_1") (pintype "passive"))
    )
    (net (code "19") (name "/+UP") (class "Default")
      (node (ref "D6") (pin "2") (pinfunction "2_2") (pintype "passive"))
      (node (ref "J6") (pin "2") (pinfunction "2_2") (pintype "passive"))
      (node (ref "RL5") (pin "1") (pinfunction "1_1") (pintype "passive"))
    )
    (net (code "20") (name "/+UP_1") (class "Default")
      (node (ref "J6A") (pin "2") (pinfunction "2_2") (pintype "passive"))
      (node (ref "KIEM TRA PIN") (pin "2") (pinfunction "2_2") (pintype "passive"))
    )
    (net (code "35") (name "/12A") (class "Default")
      (node (ref "D14") (pin "1") (pinfunction "1_1") (pintype "passive"))
      (node (ref "D14") (pin "3") (pinfunction "3_3") (pintype "passive"))
      (node (ref "J9") (pin "3") (pinfunction "3_3") (pintype "passive"))
      (node (ref "J9") (pin "4") (pinfunction "4_4") (pintype "passive"))
    )
    (net (code "36") (name "/AC1") (class "Default")
      (node (ref "AC") (pin "2") (pinfunction "N_2") (pintype "power_in"))
    )
    (net (code "37") (name "/AC2") (class "Default")
      (node (ref "AC") (pin "1") (pinfunction "L_1") (pintype "power_in"))
    )
    (net (code "38") (name "/D+") (class "Default")
      (node (ref "U27") (pin "15") (pinfunction "USBDP_15") (pintype "passive"))
      (node (ref "U5") (pin "2") (pinfunction "DP4_2") (pintype "passive"))
    )
    (net (code "39") (name "/D-") (class "Default")
      (node (ref "U27") (pin "16") (pinfunction "USBDM_16") (pintype "passive"))
      (node (ref "U5") (pin "1") (pinfunction "DM4_1") (pintype "passive"))
    )
    (net (code "42") (name "/GND_3") (class "Default")
      (node (ref "J6A") (pin "1") (pinfunction "1_1") (pintype "passive"))
      (node (ref "QUA TAI") (pin "2") (pinfunction "K_2") (pintype "passive"))
    )
    (net (code "45") (name "/MISO") (class "Default")
      (node (ref "J10") (pin "9") (pinfunction "9_9") (pintype "passive"))
      (node (ref "U11") (pin "16") (pinfunction "PB4_(MISO)_16") (pintype "bidirectional"))
    )
    (net (code "46") (name "/MOSI") (class "Default")
      (node (ref "J10") (pin "1") (pinfunction "1_1") (pintype "passive"))
      (node (ref "U11") (pin "15") (pinfunction "PB3_(MOSI/OC2)_15") (pintype "bidirectional"))
    )
    (net (code "47") (name "/RST") (class "Default")
      (node (ref "C14") (pin "2") (pinfunction "2_2") (pintype "passive"))
      (node (ref "J10") (pin "5") (pinfunction "5_5") (pintype "passive"))
      (node (ref "R23") (pin "1") (pinfunction "1_1") (pintype "passive"))
      (node (ref "U11") (pin "29") (pinfunction "PC6_(~{RESET})_29") (pintype "bidirectional"))
    )
    (net (code "48") (name "/SCK") (class "Default")
      (node (ref "J10") (pin "7") (pinfunction "7_7") (pintype "passive"))
      (node (ref "U11") (pin "17") (pinfunction "PB5_(SCK)_17") (pintype "bidirectional"))
    )
    (net (code "49") (name "/SW") (class "Default")
      (node (ref "D3") (pin "1") (pinfunction "1_1") (pintype "passive"))
      (node (ref "D3") (pin "3") (pinfunction "3_3") (pintype "passive"))
      (node (ref "J6") (pin "7") (pinfunction "7_7") (pintype "power_in"))
      (node (ref "RL2") (pin "3") (pinfunction "3_3") (pintype "passive"))
    )
    (net (code "50") (name "/USB_DN") (class "Default")
      (node (ref "U5") (pin "10") (pinfunction "DMU_10") (pintype "passive"))
      (node (ref "USB M") (pin "2") (pinfunction "2_2") (pintype "passive"))
    )
    (net (code "51") (name "/USB_DP") (class "Default")
      (node (ref "U5") (pin "11") (pinfunction "DPU_11") (pintype "passive"))
      (node (ref "USB M") (pin "3") (pinfunction "3_3") (pintype "passive"))
    )
    (net (code "52") (name "5V") (class "Default")
      (node (ref "USB1") (pin "1") (pinfunction "1_1") (pintype "passive"))
      (node (ref "USB2") (pin "1") (pinfunction "1_1") (pintype "passive"))
      (node (ref "USB3") (pin "1") (pinfunction "1_1") (pintype "passive"))
    )
    (net (code "53") (name "GND") (class "Default")
      (node (ref "C1") (pin "1") (pinfunction "1_1") (pintype "passive"))
      (node (ref "C10") (pin "1") (pinfunction "1_1") (pintype "passive"))
      (node (ref "C11") (pin "1") (pinfunction "1_1") (pintype "passive"))
      (node (ref "C14") (pin "1") (pinfunction "1_1") (pintype "passive"))
      (node (ref "C16") (pin "2") (pinfunction "2_2") (pintype "passive"))
      (node (ref "C17") (pin "2") (pinfunction "2_2") (pintype "passive"))
      (node (ref "C18") (pin "1") (pinfunction "1_1") (pintype "passive"))
      (node (ref "C19") (pin "1") (pinfunction "1_1") (pintype "passive"))
      (node (ref "C2") (pin "2") (pinfunction "2_2") (pintype "passive"))
      (node (ref "C20") (pin "2") (pinfunction "2_2") (pintype "passive"))
      (node (ref "C21") (pin "2") (pinfunction "2_2") (pintype "passive"))
      (node (ref "C22") (pin "1") (pinfunction "1_1") (pintype "passive"))
      (node (ref "C23") (pin "2") (pinfunction "2_2") (pintype "passive"))
      (node (ref "C24") (pin "2") (pinfunction "2_2") (pintype "passive"))
      (node (ref "C25") (pin "2") (pinfunction "2_2") (pintype "passive"))
      (node (ref "C26") (pin "2") (pinfunction "2_2") (pintype "passive"))
      (node (ref "C27") (pin "1") (pinfunction "1_1") (pintype "passive"))
      (node (ref "C30") (pin "2") (pinfunction "2_2") (pintype "passive"))
      (node (ref "C31") (pin "2") (pinfunction "2_2") (pintype "passive"))
      (node (ref "C32") (pin "2") (pinfunction "2_2") (pintype "passive"))
      (node (ref "C33") (pin "1") (pinfunction "1_1") (pintype "passive"))
      (node (ref "C34") (pin "2") (pinfunction "2_2") (pintype "passive"))
      (node (ref "C35") (pin "1") (pinfunction "1_1") (pintype "passive"))
      (node (ref "C4") (pin "1") (pinfunction "1_1") (pintype "passive"))
      (node (ref "C41") (pin "2") (pinfunction "2_2") (pintype "passive"))
      (node (ref "C42") (pin "2") (pinfunction "2_2") (pintype "passive"))
      (node (ref "C43") (pin "2") (pinfunction "2_2") (pintype "passive"))
      (node (ref "C44") (pin "2") (pinfunction "2_2") (pintype "passive"))
      (node (ref "C47") (pin "1") (pinfunction "1_1") (pintype "passive"))
      (node (ref "C48") (pin "2") (pinfunction "2_2") (pintype "passive"))
      (node (ref "C5") (pin "1") (pinfunction "1_1") (pintype "passive"))
      (node (ref "C50") (pin "2") (pinfunction "2_2") (pintype "passive"))
      (node (ref "C51") (pin "2") (pinfunction "2_2") (pintype "passive"))
      (node (ref "C52") (pin "2") (pinfunction "2_2") (pintype "passive"))
      (node (ref "C53") (pin "2") (pinfunction "2_2") (pintype "passive"))
      (node (ref "C54") (pin "2") (pinfunction "2_2") (pintype "passive"))
      (node (ref "C60") (pin "1") (pinfunction "1_1") (pintype "passive"))
      (node (ref "C61") (pin "1") (pinfunction "1_1") (pintype "passive"))
      (node (ref "C62") (pin "1") (pinfunction "1_1") (pintype "passive"))
      (node (ref "C63") (pin "1") (pinfunction "1_1") (pintype "passive"))
      (node (ref "C64") (pin "1") (pinfunction "1_1") (pintype "passive"))
      (node (ref "C65") (pin "1") (pinfunction "1_1") (pintype "passive"))
      (node (ref "C66") (pin "2") (pinfunction "2_2") (pintype "passive"))
      (node (ref "C67") (pin "2") (pinfunction "2_2") (pintype "passive"))
      (node (ref "C68") (pin "1") (pinfunction "1_1") (pintype "passive"))
      (node (ref "D15") (pin "2") (pinfunction "2_2") (pintype "passive"))
      (node (ref "D5") (pin "2") (pinfunction "2_2") (pintype "passive"))
      (node (ref "J1") (pin "1") (pinfunction "1_1") (pintype "passive"))
      (node (ref "J1") (pin "2") (pinfunction "2_2") (pintype "passive"))
      (node (ref "J10") (pin "10") (pinfunction "10_10") (pintype "passive"))
      (node (ref "J10") (pin "4") (pinfunction "4_4") (pintype "passive"))
      (node (ref "J10") (pin "6") (pinfunction "6_6") (pintype "passive"))
      (node (ref "J10") (pin "8") (pinfunction "8_8") (pintype "passive"))
      (node (ref "J1A") (pin "1") (pinfunction "1_1") (pintype "passive"))
      (node (ref "J1A") (pin "2") (pinfunction "2_2") (pintype "passive"))
      (node (ref "J2") (pin "1") (pinfunction "1_1") (pintype "passive"))
      (node (ref "J2") (pin "2") (pinfunction "2_2") (pintype "passive"))
      (node (ref "J5") (pin "3") (pinfunction "3_3") (pintype "passive"))
      (node (ref "J5") (pin "4") (pinfunction "4_4") (pintype "passive"))
      (node (ref "J5A") (pin "3") (pinfunction "3_3") (pintype "passive"))
      (node (ref "J5A") (pin "4") (pinfunction "4_4") (pintype "passive"))
      (node (ref "J6") (pin "1") (pinfunction "1_1") (pintype "passive"))
      (node (ref "J6") (pin "6") (pinfunction "6_6") (pintype "power_in"))
      (node (ref "J7") (pin "1") (pinfunction "1_1") (pintype "passive"))
      (node (ref "J9") (pin "1") (pinfunction "1_1") (pintype "passive"))
      (node (ref "J9") (pin "2") (pinfunction "2_2") (pintype "passive"))
      (node (ref "Q1") (pin "3") (pinfunction "S_3") (pintype "passive"))
      (node (ref "Q4") (pin "3") (pinfunction "S_3") (pintype "passive"))
      (node (ref "Q5") (pin "3") (pinfunction "S_3") (pintype "passive"))
      (node (ref "Q6") (pin "3") (pinfunction "S_3") (pintype "passive"))
      (node (ref "R12") (pin "2") (pinfunction "2_2") (pintype "passive"))
      (node (ref "R3") (pin "2") (pinfunction "2_2") (pintype "passive"))
      (node (ref "R32") (pin "1") (pinfunction "1_1") (pintype "passive"))
      (node (ref "R33") (pin "1") (pinfunction "1_1") (pintype "passive"))
      (node (ref "R35") (pin "1") (pinfunction "1_1") (pintype "passive"))
      (node (ref "R64") (pin "1") (pinfunction "1_1") (pintype "passive"))
      (node (ref "R68") (pin "1") (pinfunction "1_1") (pintype "passive"))
      (node (ref "R70") (pin "1") (pinfunction "1_1") (pintype "passive"))
      (node (ref "R8") (pin "1") (pinfunction "1_1") (pintype "passive"))
      (node (ref "TN2") (pin "1") (pinfunction "1_1") (pintype "power_in"))
      (node (ref "TN2") (pin "2") (pinfunction "2_2") (pintype "power_in"))
      (node (ref "U1") (pin "2") (pinfunction "GND_2") (pintype "passive"))
      (node (ref "U10") (pin "1") (pinfunction "ADJ_1") (pintype "input"))
      (node (ref "U11") (pin "21") (pinfunction "GND_21") (pintype "power_in"))
      (node (ref "U11") (pin "3") (pinfunction "GND_3") (pintype "power_in"))
      (node (ref "U11") (pin "5") (pinfunction "GND_5") (pintype "power_in"))
      (node (ref "U12") (pin "2") (pinfunction "GND_2") (pintype "power_in"))
      (node (ref "U15") (pin "1") (pinfunction "GND_1") (pintype "passive"))
      (node (ref "U27") (pin "18") (pinfunction "GND_18") (pintype "passive"))
      (node (ref "U27") (pin "21") (pinfunction "GND_21") (pintype "passive"))
      (node (ref "U27") (pin "25") (pinfunction "AGND_25") (pintype "passive"))
      (node (ref "U27") (pin "26") (pinfunction "TEST_26") (pintype "passive"))
      (node (ref "U27") (pin "7") (pinfunction "GND_7") (pintype "passive"))
      (node (ref "U3") (pin "2") (pinfunction "GND_2") (pintype "passive"))
      (node (ref "U3") (pin "3") (pinfunction "OUT-_3") (pintype "passive"))
      (node (ref "U5") (pin "12") (pinfunction "VDD5_12") (pintype "passive"))
      (node (ref "U5") (pin "14") (pinfunction "VSS_14") (pintype "passive"))
      (node (ref "U6") (pin "4") (pinfunction "A/K_4") (pintype "passive"))
      (node (ref "U7") (pin "4") (pinfunction "A/K_4") (pintype "passive"))
      (node (ref "U8") (pin "2") (pinfunction "GND_2") (pintype "passive"))
      (node (ref "U8") (pin "3") (pinfunction "GND_3") (pintype "passive"))
      (node (ref "USB1") (pin "4") (pinfunction "4_4") (pintype "passive"))
      (node (ref "USB2") (pin "4") (pinfunction "4_4") (pintype "passive"))
      (node (ref "USB3") (pin "4") (pinfunction "4_4") (pintype "passive"))
      (node (ref "VR1") (pin "1") (pinfunction "TOP_1") (pintype "passive"))
      (node (ref "VR2") (pin "1") (pinfunction "TOP_1") (pintype "passive"))
      (node (ref "VR3") (pin "1") (pinfunction "TOP_1") (pintype "passive"))
    )
    (net (code "54") (name "Net-(C2-Pad1)") (class "Default")
      (node (ref "C2") (pin "1") (pinfunction "1_1") (pintype "passive"))
      (node (ref "D4") (pin "1") (pinfunction "1_1") (pintype "passive"))
      (node (ref "R6") (pin "2") (pinfunction "2_2") (pintype "passive"))
    )
    (net (code "55") (name "Net-(D2-Pad1)") (class "Default")
      (node (ref "D2") (pin "1") (pinfunction "1_1") (pintype "passive"))
      (node (ref "RL2") (pin "2") (pinfunction "2_2") (pintype "passive"))
      (node (ref "U6") (pin "6") (pinfunction "A/K_6") (pintype "passive"))
    )
    (net (code "56") (name "Net-(D9-Pad1)") (class "Default")
      (node (ref "D9") (pin "1") (pinfunction "1_1") (pintype "passive"))
      (node (ref "RL4") (pin "3") (pinfunction "3_3") (pintype "passive"))
    )
    (net (code "57") (name "Net-(D10-Pad1)") (class "Default")
      (node (ref "D10") (pin "1") (pinfunction "1_1") (pintype "passive"))
      (node (ref "RL3") (pin "3") (pinfunction "3_3") (pintype "passive"))
    )
    (net (code "58") (name "Net-(D10-Pad2)") (class "Default")
      (node (ref "D10") (pin "2") (pinfunction "2_2") (pintype "passive"))
      (node (ref "D9") (pin "2") (pinfunction "2_2") (pintype "passive"))
      (node (ref "R99") (pin "2") (pinfunction "2_2") (pintype "passive"))
    )
    (net (code "59") (name "Net-(D11-Pad1)") (class "Default")
      (node (ref "D11") (pin "1") (pinfunction "1_1") (pintype "passive"))
      (node (ref "RL6") (pin "2") (pinfunction "2_2") (pintype "passive"))
    )
    (net (code "60") (name "Net-(D48-K)") (class "Default")
      (node (ref "D48") (pin "2") (pinfunction "K_2") (pintype "passive"))
      (node (ref "R61") (pin "1") (pinfunction "1_1") (pintype "passive"))
    )
    (net (code "61") (name "Net-(D49-K)") (class "Default")
      (node (ref "D49") (pin "2") (pinfunction "K_2") (pintype "passive"))
      (node (ref "R62") (pin "1") (pinfunction "1_1") (pintype "passive"))
    )
    (net (code "62") (name "Net-(J6A-Pad3)") (class "Default")
      (node (ref "J6A") (pin "3") (pinfunction "3_3") (pintype "passive"))
      (node (ref "KIEM TRA PIN") (pin "1") (pinfunction "1_1") (pintype "passive"))
    )
    (net (code "63") (name "Net-(J6A-Pad7)") (class "Default")
      (node (ref "J6A") (pin "7") (pinfunction "7_7") (pintype "power_in"))
      (node (ref "NGUON") (pin "2") (pinfunction "2_2") (pintype "passive"))
    )
    (net (code "64") (name "Net-(J6A-Pad8)") (class "Default")
      (node (ref "J6A") (pin "8") (pinfunction "8_8") (pintype "power_in"))
      (node (ref "NGUON") (pin "1") (pinfunction "1_1") (pintype "passive"))
    )
    (net (code "65") (name "Net-(LED NGUON-A)") (class "Default")
      (node (ref "J6A") (pin "5") (pinfunction "5_5") (pintype "passive"))
      (node (ref "LED NGUON") (pin "1") (pinfunction "A_1") (pintype "passive"))
    )
    (net (code "66") (name "Net-(LED NGUON-K)") (class "Default")
      (node (ref "J6A") (pin "6") (pinfunction "6_6") (pintype "power_in"))
      (node (ref "LED NGUON") (pin "2") (pinfunction "K_2") (pintype "passive"))
    )
    (net (code "67") (name "Net-(Q1-D)") (class "Default")
      (node (ref "D1") (pin "1") (pinfunction "1_1") (pintype "passive"))
      (node (ref "Q1") (pin "2") (pinfunction "D_2") (pintype "passive"))
      (node (ref "RL1") (pin "2") (pinfunction "2_2") (pintype "passive"))
    )
    (net (code "68") (name "Net-(Q1-G)") (class "Default")
      (node (ref "C1") (pin "2") (pinfunction "2_2") (pintype "passive"))
      (node (ref "Q1") (pin "1") (pinfunction "G_1") (pintype "passive"))
      (node (ref "R2") (pin "2") (pinfunction "2_2") (pintype "passive"))
      (node (ref "R3") (pin "1") (pinfunction "1_1") (pintype "passive"))
      (node (ref "U7") (pin "6") (pinfunction "A/K_6") (pintype "passive"))
    )
    (net (code "69") (name "Net-(Q4-D)") (class "Default")
      (node (ref "D6") (pin "1") (pinfunction "1_1") (pintype "passive"))
      (node (ref "Q4") (pin "2") (pinfunction "D_2") (pintype "passive"))
      (node (ref "RL5") (pin "2") (pinfunction "2_2") (pintype "passive"))
    )
    (net (code "70") (name "Net-(Q4-G)") (class "Default")
      (node (ref "Q4") (pin "1") (pinfunction "G_1") (pintype "passive"))
      (node (ref "R34") (pin "2") (pinfunction "2_2") (pintype "passive"))
      (node (ref "R35") (pin "2") (pinfunction "2_2") (pintype "passive"))
    )
    (net (code "71") (name "Net-(Q5-D)") (class "Default")
      (node (ref "D8") (pin "1") (pinfunction "1_1") (pintype "passive"))
      (node (ref "Q5") (pin "2") (pinfunction "D_2") (pintype "passive"))
      (node (ref "RL4") (pin "2") (pinfunction "2_2") (pintype "passive"))
    )
    (net (code "72") (name "Net-(Q5-G)") (class "Default")
      (node (ref "C64") (pin "2") (pinfunction "2_2") (pintype "passive"))
      (node (ref "Q5") (pin "1") (pinfunction "G_1") (pintype "passive"))
      (node (ref "R68") (pin "2") (pinfunction "2_2") (pintype "passive"))
      (node (ref "R69") (pin "1") (pinfunction "1_1") (pintype "passive"))
    )
    (net (code "73") (name "Net-(Q6-D)") (class "Default")
      (node (ref "D7") (pin "1") (pinfunction "1_1") (pintype "passive"))
      (node (ref "Q6") (pin "2") (pinfunction "D_2") (pintype "passive"))
      (node (ref "RL3") (pin "2") (pinfunction "2_2") (pintype "passive"))
    )
    (net (code "74") (name "Net-(Q6-G)") (class "Default")
      (node (ref "C65") (pin "2") (pinfunction "2_2") (pintype "passive"))
      (node (ref "Q6") (pin "1") (pinfunction "G_1") (pintype "passive"))
      (node (ref "R70") (pin "2") (pinfunction "2_2") (pintype "passive"))
      (node (ref "R71") (pin "1") (pinfunction "1_1") (pintype "passive"))
    )
    (net (code "75") (name "Net-(QUA TAI-A)") (class "Default")
      (node (ref "J6A") (pin "4") (pinfunction "4_4") (pintype "passive"))
      (node (ref "QUA TAI") (pin "1") (pinfunction "A_1") (pintype "passive"))
    )
    (net (code "76") (name "Net-(R9-Pad1)") (class "Default")
      (node (ref "R9") (pin "1") (pinfunction "1_1") (pintype "passive"))
      (node (ref "RL2") (pin "4") (pinfunction "4_4") (pintype "passive"))
    )
    (net (code "77") (name "Net-(R12-Pad1)") (class "Default")
      (node (ref "R12") (pin "1") (pinfunction "1_1") (pintype "passive"))
      (node (ref "RL1") (pin "4") (pinfunction "4_4") (pintype "passive"))
    )
    (net (code "78") (name "Net-(TA-OSC1)") (class "Default")
      (node (ref "C43") (pin "1") (pinfunction "1_1") (pintype "passive"))
      (node (ref "R63") (pin "2") (pinfunction "2_2") (pintype "passive"))
      (node (ref "TA") (pin "1") (pinfunction "OSC1_1") (pintype "passive"))
      (node (ref "U5") (pin "15") (pinfunction "XIN_15") (pintype "passive"))
    )
    (net (code "79") (name "Net-(TA-OSC2)") (class "Default")
      (node (ref "C44") (pin "1") (pinfunction "1_1") (pintype "passive"))
      (node (ref "R63") (pin "1") (pinfunction "1_1") (pintype "passive"))
      (node (ref "TA") (pin "2") (pinfunction "OSC2_2") (pintype "passive"))
      (node (ref "U5") (pin "16") (pinfunction "XOUT_16") (pintype "passive"))
    )
    (net (code "80") (name "Net-(TA2-OSC1)") (class "Default")
      (node (ref "C60") (pin "2") (pinfunction "2_2") (pintype "passive"))
      (node (ref "TA2") (pin "1") (pinfunction "OSC1_1") (pintype "passive"))
      (node (ref "U11") (pin "8") (pinfunction "PB7_(XTAL2/TOSC2)_8") (pintype "bidirectional"))
    )
    (net (code "81") (name "Net-(TA2-OSC2)") (class "Default")
      (node (ref "C61") (pin "2") (pinfunction "2_2") (pintype "passive"))
      (node (ref "TA2") (pin "2") (pinfunction "OSC2_2") (pintype "passive"))
      (node (ref "U11") (pin "7") (pinfunction "PB6_(XTAL1/TOSC1)_7") (pintype "bidirectional"))
    )
    (net (code "82") (name "Net-(U5-DM1)") (class "Default")
      (node (ref "U5") (pin "7") (pinfunction "DM1_7") (pintype "passive"))
      (node (ref "USB1") (pin "2") (pinfunction "2_2") (pintype "passive"))
    )
    (net (code "83") (name "Net-(U5-DM2)") (class "Default")
      (node (ref "U5") (pin "5") (pinfunction "DM2_5") (pintype "passive"))
      (node (ref "USB2") (pin "2") (pinfunction "2_2") (pintype "passive"))
    )
    (net (code "84") (name "Net-(U5-DM3)") (class "Default")
      (node (ref "U5") (pin "3") (pinfunction "DM3_3") (pintype "passive"))
      (node (ref "USB3") (pin "2") (pinfunction "2_2") (pintype "passive"))
    )
    (net (code "85") (name "Net-(U5-DP1)") (class "Default")
      (node (ref "U5") (pin "8") (pinfunction "DP1_8") (pintype "passive"))
      (node (ref "USB1") (pin "3") (pinfunction "3_3") (pintype "passive"))
    )
    (net (code "86") (name "Net-(U5-DP2)") (class "Default")
      (node (ref "U5") (pin "6") (pinfunction "DP2_6") (pintype "passive"))
      (node (ref "USB2") (pin "3") (pinfunction "3_3") (pintype "passive"))
    )
    (net (code "87") (name "Net-(U5-DP3)") (class "Default")
      (node (ref "U5") (pin "4") (pinfunction "DP3_4") (pintype "passive"))
      (node (ref "USB3") (pin "3") (pinfunction "3_3") (pintype "passive"))
    )
    (net (code "88") (name "Net-(U5-REXT)") (class "Default")
      (node (ref "R64") (pin "2") (pinfunction "2_2") (pintype "passive"))
      (node (ref "U5") (pin "9") (pinfunction "REXT_9") (pintype "passive"))
    )
    (net (code "89") (name "Net-(U6-A)") (class "Default")
      (node (ref "D4") (pin "2") (pinfunction "2_2") (pintype "passive"))
      (node (ref "U6") (pin "1") (pinfunction "A_1") (pintype "passive"))
    )
    (net (code "90") (name "Net-(U6-K)") (class "Default")
      (node (ref "R8") (pin "2") (pinfunction "2_2") (pintype "passive"))
      (node (ref "RL2") (pin "5") (pinfunction "5_5") (pintype "passive"))
      (node (ref "U6") (pin "2") (pinfunction "K_2") (pintype "passive"))
    )
    (net (code "91") (name "Net-(U7-A)") (class "Default")
      (node (ref "C4") (pin "2") (pinfunction "2_2") (pintype "passive"))
      (node (ref "R9") (pin "2") (pinfunction "2_2") (pintype "passive"))
      (node (ref "U7") (pin "1") (pinfunction "A_1") (pintype "passive"))
    )
    (net (code "92") (name "Net-(U7-K)") (class "Default")
      (node (ref "D5") (pin "1") (pinfunction "1_1") (pintype "passive"))
      (node (ref "U7") (pin "2") (pinfunction "K_2") (pintype "passive"))
    )
    (net (code "93") (name "Net-(U11-AREF)") (class "Default")
      (node (ref "C62") (pin "2") (pinfunction "2_2") (pintype "passive"))
      (node (ref "U11") (pin "20") (pinfunction "AREF_20") (pintype "power_in"))
    )
    (net (code "94") (name "Net-(U11-PC0_(ADC0))") (class "Default")
      (node (ref "C10") (pin "2") (pinfunction "2_2") (pintype "passive"))
      (node (ref "U11") (pin "23") (pinfunction "PC0_(ADC0)_23") (pintype "bidirectional"))
      (node (ref "VR1") (pin "2") (pinfunction "TAP_2") (pintype "passive"))
    )
    (net (code "95") (name "Net-(U11-PC1_(ADC1))") (class "Default")
      (node (ref "C11") (pin "2") (pinfunction "2_2") (pintype "passive"))
      (node (ref "U11") (pin "24") (pinfunction "PC1_(ADC1)_24") (pintype "bidirectional"))
      (node (ref "VR2") (pin "2") (pinfunction "TAP_2") (pintype "passive"))
    )
    (net (code "96") (name "Net-(U11-PC2_(ADC2))") (class "Default")
      (node (ref "C63") (pin "2") (pinfunction "2_2") (pintype "passive"))
      (node (ref "U11") (pin "25") (pinfunction "PC2_(ADC2)_25") (pintype "bidirectional"))
      (node (ref "VR3") (pin "2") (pinfunction "TAP_2") (pintype "passive"))
    )
    (net (code "97") (name "Net-(U11-PD0_(RXD))") (class "Default")
      (node (ref "U11") (pin "30") (pinfunction "PD0_(RXD)_30") (pintype "bidirectional"))
      (node (ref "U27") (pin "1") (pinfunction "TXD_1") (pintype "passive"))
    )
    (net (code "98") (name "Net-(U11-PD1_(TXD))") (class "Default")
      (node (ref "U11") (pin "31") (pinfunction "PD1_(TXD)_31") (pintype "bidirectional"))
      (node (ref "U27") (pin "5") (pinfunction "RXD_5") (pintype "passive"))
    )
    (net (code "99") (name "Net-(U11-PD2_(INT0))") (class "Default")
      (node (ref "R71") (pin "2") (pinfunction "2_2") (pintype "passive"))
      (node (ref "U11") (pin "32") (pinfunction "PD2_(INT0)_32") (pintype "bidirectional"))
    )
    (net (code "100") (name "Net-(U11-PD3_(INT1))") (class "Default")
      (node (ref "R69") (pin "2") (pinfunction "2_2") (pintype "passive"))
      (node (ref "U11") (pin "1") (pinfunction "PD3_(INT1)_1") (pintype "bidirectional"))
    )
    (net (code "101") (name "Net-(U15-FB)") (class "Default")
      (node (ref "C55") (pin "1") (pinfunction "1_1") (pintype "passive"))
      (node (ref "R31") (pin "1") (pinfunction "1_1") (pintype "passive"))
      (node (ref "R32") (pin "2") (pinfunction "2_2") (pintype "passive"))
      (node (ref "R33") (pin "2") (pinfunction "2_2") (pintype "passive"))
      (node (ref "U15") (pin "2") (pinfunction "FB_2") (pintype "passive"))
    )
    (net (code "102") (name "Net-(U15-SW)") (class "Default")
      (node (ref "D15") (pin "1") (pinfunction "1_1") (pintype "passive"))
      (node (ref "L1") (pin "1") (pinfunction "1_1") (pintype "passive"))
      (node (ref "U15") (pin "3") (pinfunction "SW_3") (pintype "passive"))
    )
    (net (code "103") (name "Net-(U15-VC)") (class "Default")
      (node (ref "C49") (pin "2") (pinfunction "2_2") (pintype "passive"))
      (node (ref "U15") (pin "4") (pinfunction "VC_4") (pintype "passive"))
    )
    (net (code "104") (name "Net-(U27-3V3OUT)") (class "Default")
      (node (ref "C42") (pin "1") (pinfunction "1_1") (pintype "passive"))
      (node (ref "U27") (pin "17") (pinfunction "3V3OUT_17") (pintype "passive"))
    )
    (net (code "105") (name "Net-(U27-CBUS0)") (class "Default")
      (node (ref "R61") (pin "2") (pinfunction "2_2") (pintype "passive"))
      (node (ref "U27") (pin "23") (pinfunction "CBUS0_23") (pintype "passive"))
    )
    (net (code "106") (name "Net-(U27-CBUS1)") (class "Default")
      (node (ref "R62") (pin "2") (pinfunction "2_2") (pintype "passive"))
      (node (ref "U27") (pin "22") (pinfunction "CBUS1_22") (pintype "passive"))
    )
    (net (code "107") (name "Net-(VR1-BOT)") (class "Default")
      (node (ref "R65") (pin "1") (pinfunction "1_1") (pintype "passive"))
      (node (ref "VR1") (pin "3") (pinfunction "BOT_3") (pintype "passive"))
    )
    (net (code "108") (name "Net-(VR2-BOT)") (class "Default")
      (node (ref "R66") (pin "1") (pinfunction "1_1") (pintype "passive"))
      (node (ref "VR2") (pin "3") (pinfunction "BOT_3") (pintype "passive"))
    )
    (net (code "109") (name "Net-(VR3-BOT)") (class "Default")
      (node (ref "R67") (pin "1") (pinfunction "1_1") (pintype "passive"))
      (node (ref "VR3") (pin "3") (pinfunction "BOT_3") (pintype "passive"))
    )
    (net (code "110") (name "unconnected-(AC-E-Pad3)") (class "Default")
      (node (ref "AC") (pin "3") (pinfunction "E_3") (pintype "power_in"))
    )
    (net (code "111") (name "unconnected-(J1-Pad3)") (class "Default")
      (node (ref "J1") (pin "3") (pinfunction "3_3") (pintype "passive"))
    )
    (net (code "112") (name "unconnected-(J1A-Pad3)") (class "Default")
      (node (ref "J1A") (pin "3") (pinfunction "3_3") (pintype "passive"))
    )
    (net (code "113") (name "unconnected-(J2A-Pad1)") (class "Default")
      (node (ref "J2A") (pin "1") (pinfunction "1_1") (pintype "passive"))
    )
    (net (code "114") (name "unconnected-(J2A-Pad2)") (class "Default")
      (node (ref "J2A") (pin "2") (pinfunction "2_2") (pintype "passive"))
    )
    (net (code "115") (name "unconnected-(J2A-Pad3)") (class "Default")
      (node (ref "J2A") (pin "3") (pinfunction "3_3") (pintype "passive"))
    )
    (net (code "116") (name "unconnected-(J2A-Pad4)") (class "Default")
      (node (ref "J2A") (pin "4") (pinfunction "4_4") (pintype "passive"))
    )
    (net (code "117") (name "unconnected-(J7-Pad2)") (class "Default")
      (node (ref "J7") (pin "2") (pinfunction "2_2") (pintype "passive"))
    )
    (net (code "118") (name "unconnected-(J7A-Pad1)") (class "Default")
      (node (ref "J7A") (pin "1") (pinfunction "1_1") (pintype "passive"))
    )
    (net (code "119") (name "unconnected-(J7A-Pad2)") (class "Default")
      (node (ref "J7A") (pin "2") (pinfunction "2_2") (pintype "passive"))
    )
    (net (code "120") (name "unconnected-(J7A-Pad3)") (class "Default")
      (node (ref "J7A") (pin "3") (pinfunction "3_3") (pintype "passive"))
    )
    (net (code "121") (name "unconnected-(J10-Pad3)") (class "Default")
      (node (ref "J10") (pin "3") (pinfunction "3_3") (pintype "passive"))
    )
    (net (code "122") (name "unconnected-(RL1-Pad3)") (class "Default")
      (node (ref "RL1") (pin "3") (pinfunction "3_3") (pintype "passive"))
    )
    (net (code "123") (name "unconnected-(RL3-Pad4)") (class "Default")
      (node (ref "RL3") (pin "4") (pinfunction "4_4") (pintype "passive"))
    )
    (net (code "124") (name "unconnected-(RL3-Pad7)") (class "Default")
      (node (ref "RL3") (pin "7") (pinfunction "7_7") (pintype "passive"))
    )
    (net (code "125") (name "unconnected-(RL4-Pad4)") (class "Default")
      (node (ref "RL4") (pin "4") (pinfunction "4_4") (pintype "passive"))
    )
    (net (code "126") (name "unconnected-(RL4-Pad7)") (class "Default")
      (node (ref "RL4") (pin "7") (pinfunction "7_7") (pintype "passive"))
    )
    (net (code "127") (name "unconnected-(RL5-Pad7)") (class "Default")
      (node (ref "RL5") (pin "7") (pinfunction "7_7") (pintype "passive"))
    )
    (net (code "128") (name "unconnected-(RL5-Pad8)") (class "Default")
      (node (ref "RL5") (pin "8") (pinfunction "8_8") (pintype "passive"))
    )
    (net (code "129") (name "unconnected-(RL6-Pad3)") (class "Default")
      (node (ref "RL6") (pin "3") (pinfunction "3_3") (pintype "passive"))
    )
    (net (code "130") (name "unconnected-(RL6-Pad4)") (class "Default")
      (node (ref "RL6") (pin "4") (pinfunction "4_4") (pintype "passive"))
    )
    (net (code "131") (name "unconnected-(RL6-Pad5)") (class "Default")
      (node (ref "RL6") (pin "5") (pinfunction "5_5") (pintype "passive"))
    )
    (net (code "132") (name "unconnected-(U1-GND-Pad3)") (class "Default")
      (node (ref "U1") (pin "3") (pinfunction "GND_3") (pintype "passive"))
    )
    (net (code "133") (name "unconnected-(U1-NC-Pad5)") (class "Default")
      (node (ref "U1") (pin "5") (pinfunction "NC_5") (pintype "passive"))
    )
    (net (code "134") (name "unconnected-(U3-NC-Pad5)") (class "Default")
      (node (ref "U3") (pin "5") (pinfunction "NC_5") (pintype "passive"))
    )
    (net (code "135") (name "unconnected-(U8-NC-Pad5)") (class "Default")
      (node (ref "U8") (pin "5") (pinfunction "NC_5") (pintype "passive"))
    )
    (net (code "136") (name "unconnected-(U11-ADC6-Pad19)") (class "Default")
      (node (ref "U11") (pin "19") (pinfunction "ADC6_19") (pintype "input"))
    )
    (net (code "137") (name "unconnected-(U11-ADC7-Pad22)") (class "Default")
      (node (ref "U11") (pin "22") (pinfunction "ADC7_22") (pintype "input"))
    )
    (net (code "138") (name "unconnected-(U11-PB0_(ICP1)-Pad12)") (class "Default")
      (node (ref "U11") (pin "12") (pinfunction "PB0_(ICP1)_12") (pintype "bidirectional"))
    )
    (net (code "139") (name "unconnected-(U11-PB1_(OC1A)-Pad13)") (class "Default")
      (node (ref "U11") (pin "13") (pinfunction "PB1_(OC1A)_13") (pintype "bidirectional"))
    )
    (net (code "140") (name "unconnected-(U11-PB2_(~{SS}{slash}OC1B)-Pad14)") (class "Default")
      (node (ref "U11") (pin "14") (pinfunction "PB2_(~{SS}/OC1B)_14") (pintype "bidirectional"))
    )
    (net (code "141") (name "unconnected-(U11-PC3_(ADC3)-Pad26)") (class "Default")
      (node (ref "U11") (pin "26") (pinfunction "PC3_(ADC3)_26") (pintype "bidirectional"))
    )
    (net (code "142") (name "unconnected-(U11-PC4_(ADC4{slash}SDA)-Pad27)") (class "Default")
      (node (ref "U11") (pin "27") (pinfunction "PC4_(ADC4/SDA)_27") (pintype "bidirectional"))
    )
    (net (code "143") (name "unconnected-(U11-PC5_(ADC5{slash}SCL)-Pad28)") (class "Default")
      (node (ref "U11") (pin "28") (pinfunction "PC5_(ADC5/SCL)_28") (pintype "bidirectional"))
    )
    (net (code "144") (name "unconnected-(U11-PD4_(XCK{slash}T0)-Pad2)") (class "Default")
      (node (ref "U11") (pin "2") (pinfunction "PD4_(XCK/T0)_2") (pintype "bidirectional"))
    )
    (net (code "145") (name "unconnected-(U11-PD5_(T1)-Pad9)") (class "Default")
      (node (ref "U11") (pin "9") (pinfunction "PD5_(T1)_9") (pintype "bidirectional"))
    )
    (net (code "146") (name "unconnected-(U11-PD6_(AIN0)-Pad10)") (class "Default")
      (node (ref "U11") (pin "10") (pinfunction "PD6_(AIN0)_10") (pintype "bidirectional"))
    )
    (net (code "147") (name "unconnected-(U11-PD7_(AIN1)-Pad11)") (class "Default")
      (node (ref "U11") (pin "11") (pinfunction "PD7_(AIN1)_11") (pintype "bidirectional"))
    )
    (net (code "148") (name "unconnected-(U27-CBUS2-Pad13)") (class "Default")
      (node (ref "U27") (pin "13") (pinfunction "CBUS2_13") (pintype "passive"))
    )
    (net (code "149") (name "unconnected-(U27-CBUS3-Pad14)") (class "Default")
      (node (ref "U27") (pin "14") (pinfunction "CBUS3_14") (pintype "passive"))
    )
    (net (code "150") (name "unconnected-(U27-CBUS4-Pad12)") (class "Default")
      (node (ref "U27") (pin "12") (pinfunction "CBUS4_12") (pintype "passive"))
    )
    (net (code "151") (name "unconnected-(U27-CTS#-Pad11)") (class "Default")
      (node (ref "U27") (pin "11") (pinfunction "CTS#_11") (pintype "passive"))
    )
    (net (code "152") (name "unconnected-(U27-DCD#-Pad10)") (class "Default")
      (node (ref "U27") (pin "10") (pinfunction "DCD#_10") (pintype "passive"))
    )
    (net (code "153") (name "unconnected-(U27-DSR#-Pad9)") (class "Default")
      (node (ref "U27") (pin "9") (pinfunction "DSR#_9") (pintype "passive"))
    )
    (net (code "154") (name "unconnected-(U27-DTR#-Pad2)") (class "Default")
      (node (ref "U27") (pin "2") (pinfunction "DTR#_2") (pintype "passive"))
    )
    (net (code "155") (name "unconnected-(U27-NC-Pad8)") (class "Default")
      (node (ref "U27") (pin "8") (pinfunction "NC_8") (pintype "passive"))
    )
    (net (code "156") (name "unconnected-(U27-NC-Pad24)") (class "Default")
      (node (ref "U27") (pin "24") (pinfunction "NC_24") (pintype "passive"))
    )
    (net (code "157") (name "unconnected-(U27-OSCI-Pad27)") (class "Default")
      (node (ref "U27") (pin "27") (pinfunction "OSCI_27") (pintype "passive"))
    )
    (net (code "158") (name "unconnected-(U27-OSCO-Pad28)") (class "Default")
      (node (ref "U27") (pin "28") (pinfunction "OSCO_28") (pintype "passive"))
    )
    (net (code "159") (name "unconnected-(U27-RI#-Pad6)") (class "Default")
      (node (ref "U27") (pin "6") (pinfunction "RI#_6") (pintype "passive"))
    )
    (net (code "160") (name "unconnected-(U27-RTS#-Pad3)") (class "Default")
      (node (ref "U27") (pin "3") (pinfunction "RTS#_3") (pintype "passive"))
    )
    (net (code "161") (name "unconnected-(USB M-Pad1)") (class "Default")
      (node (ref "USB M") (pin "1") (pinfunction "1_1") (pintype "passive"))
    )
    (net (code "162") (name "unconnected-(USB M-Pad4)") (class "Default")
      (node (ref "USB M") (pin "4") (pinfunction "4_4") (pintype "passive"))
    )
  )
)
